# PSPS_AVNC_SRD_fullBoard-2020-09-19.net
KiCad netlist of a schematic drawn in EAGLE
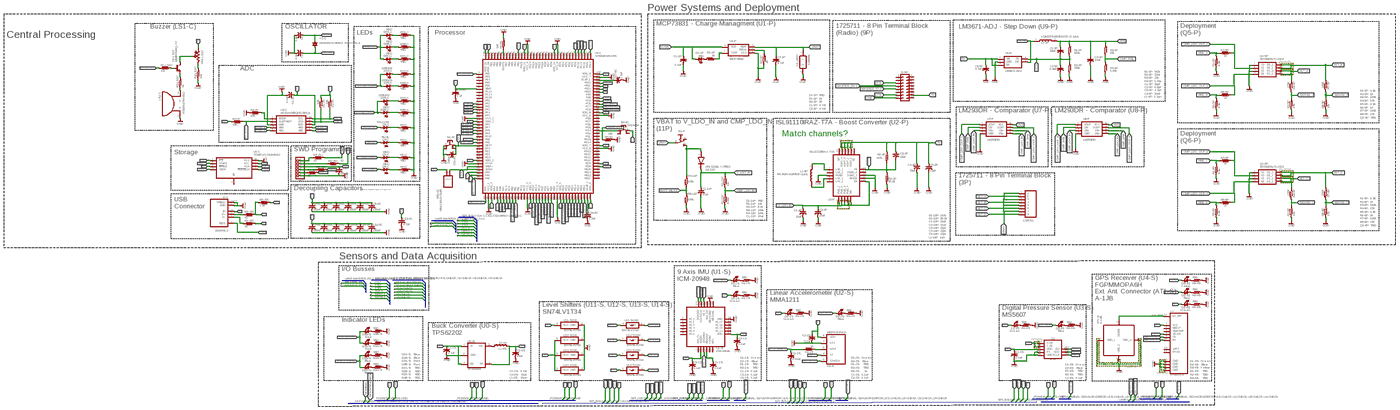
[diagram p0: schematic, sheet 1, overview]
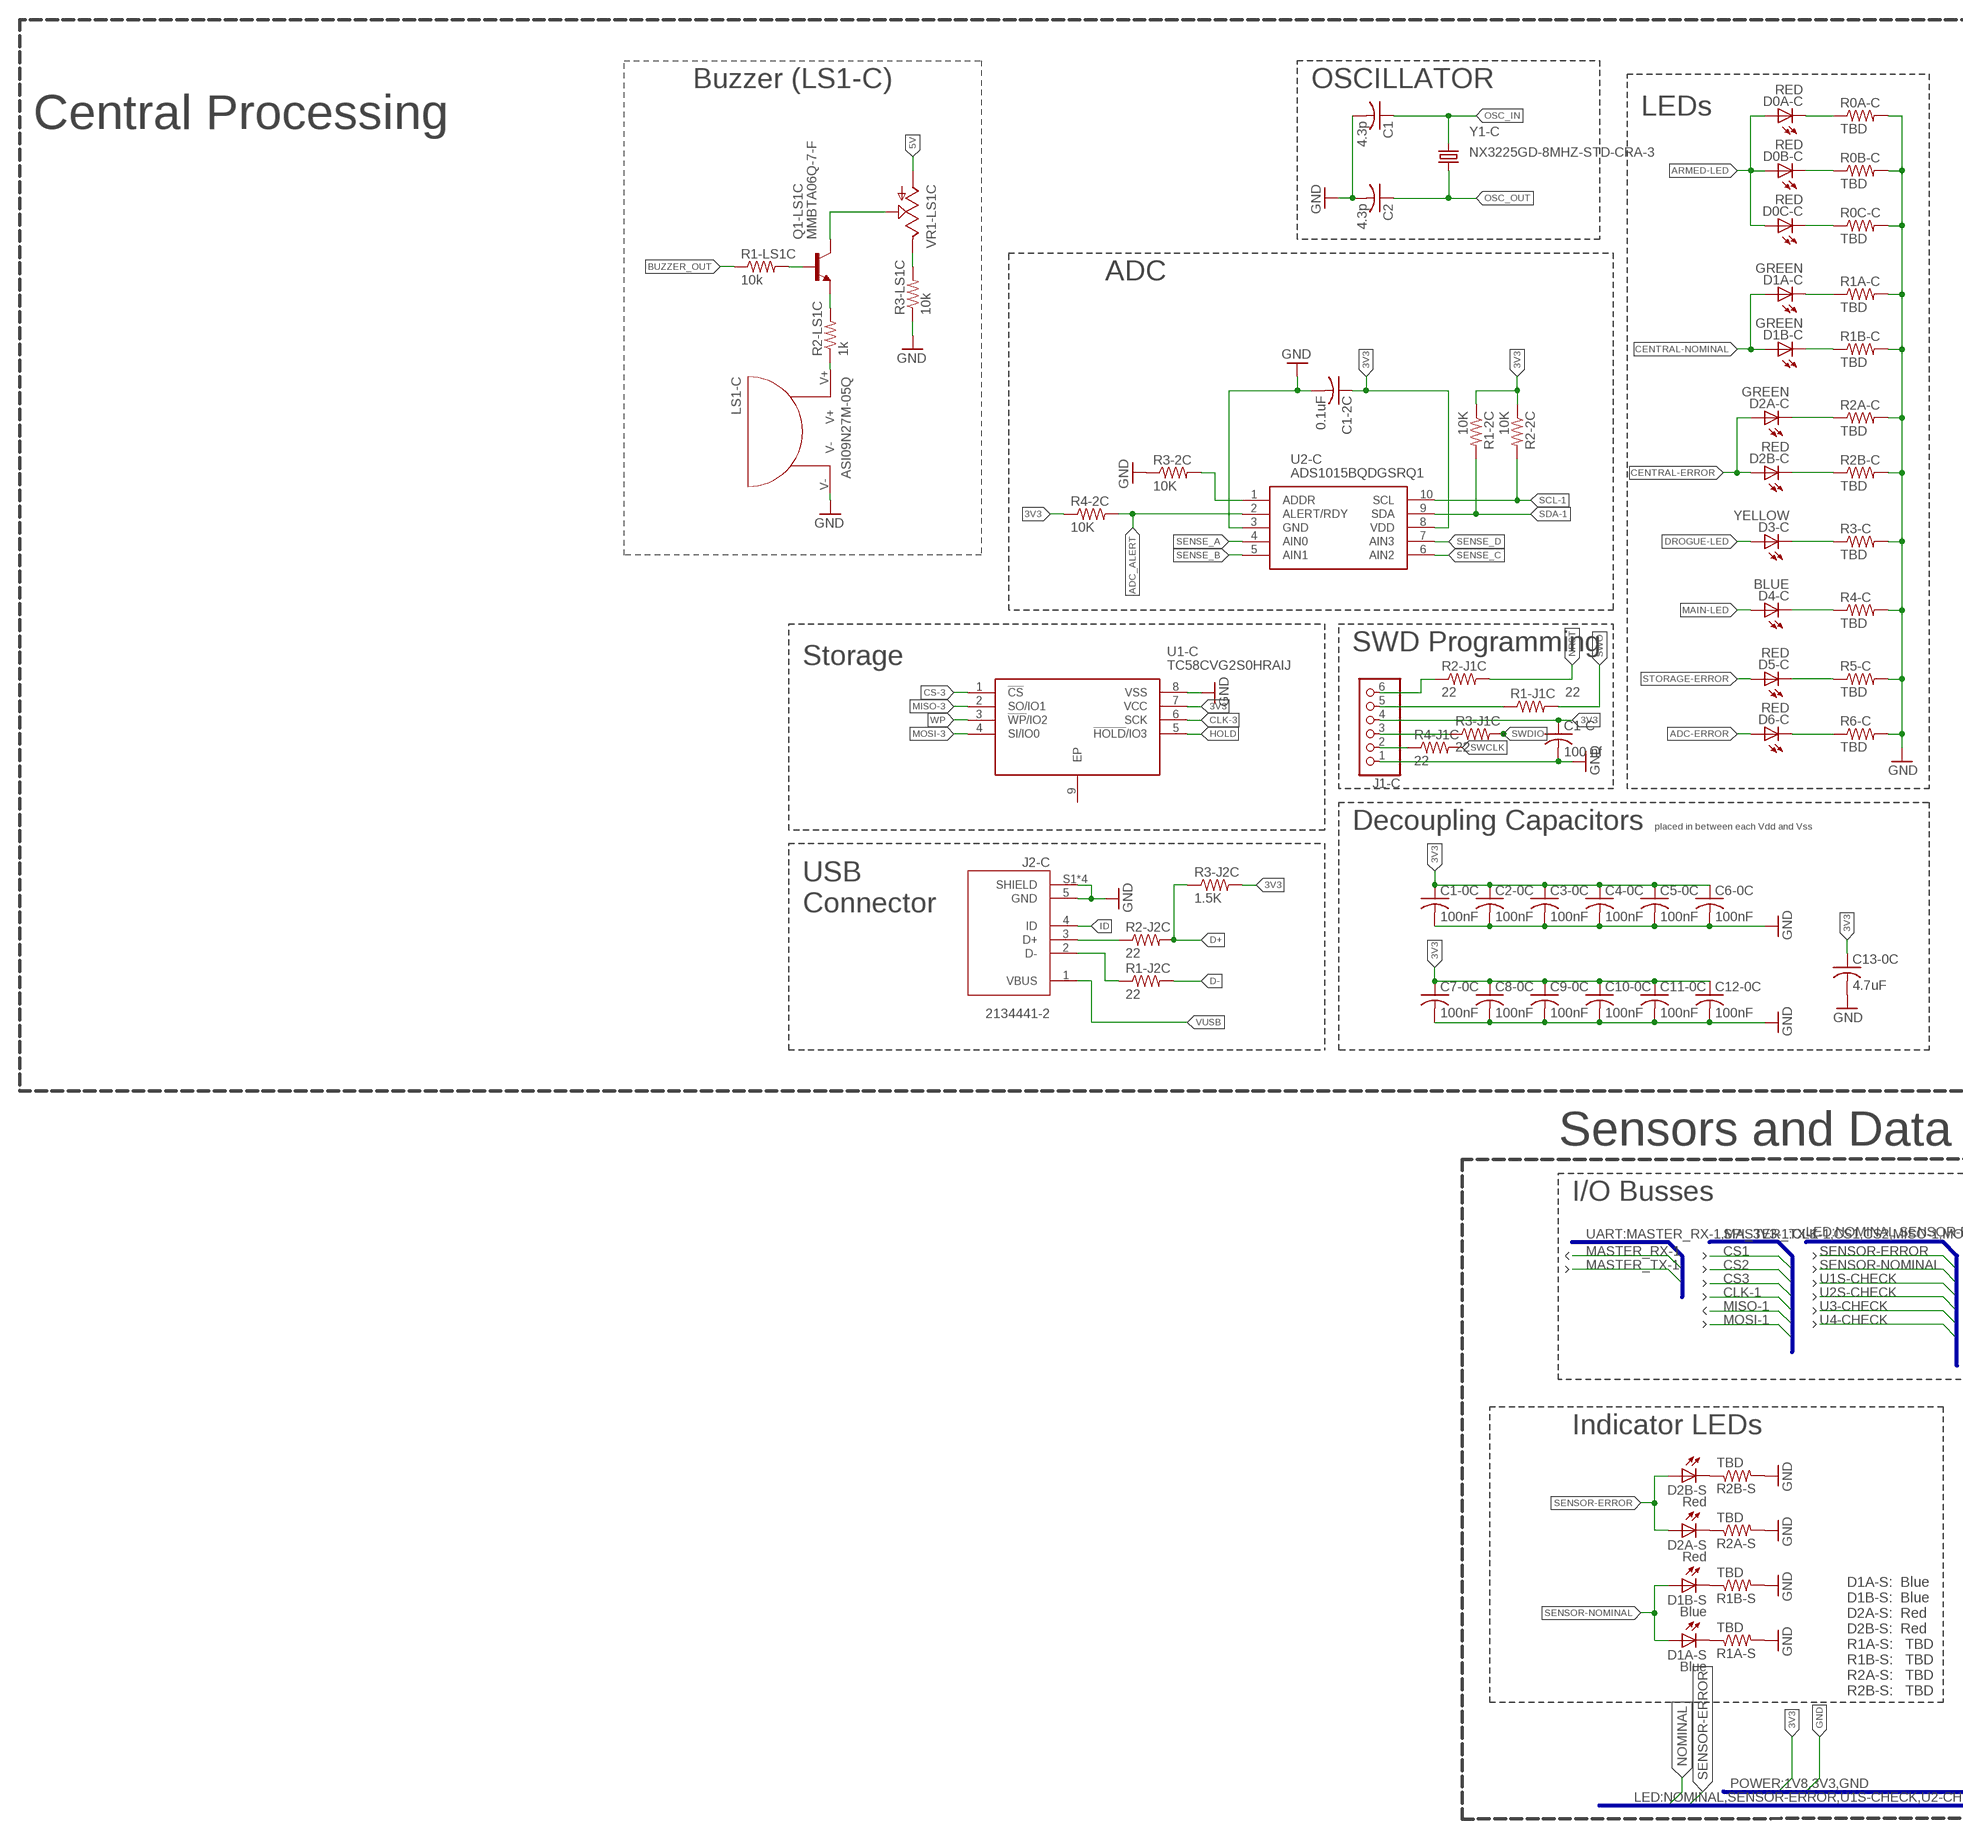
[diagram p1: schematic, sheet 1, part 1 of 4]
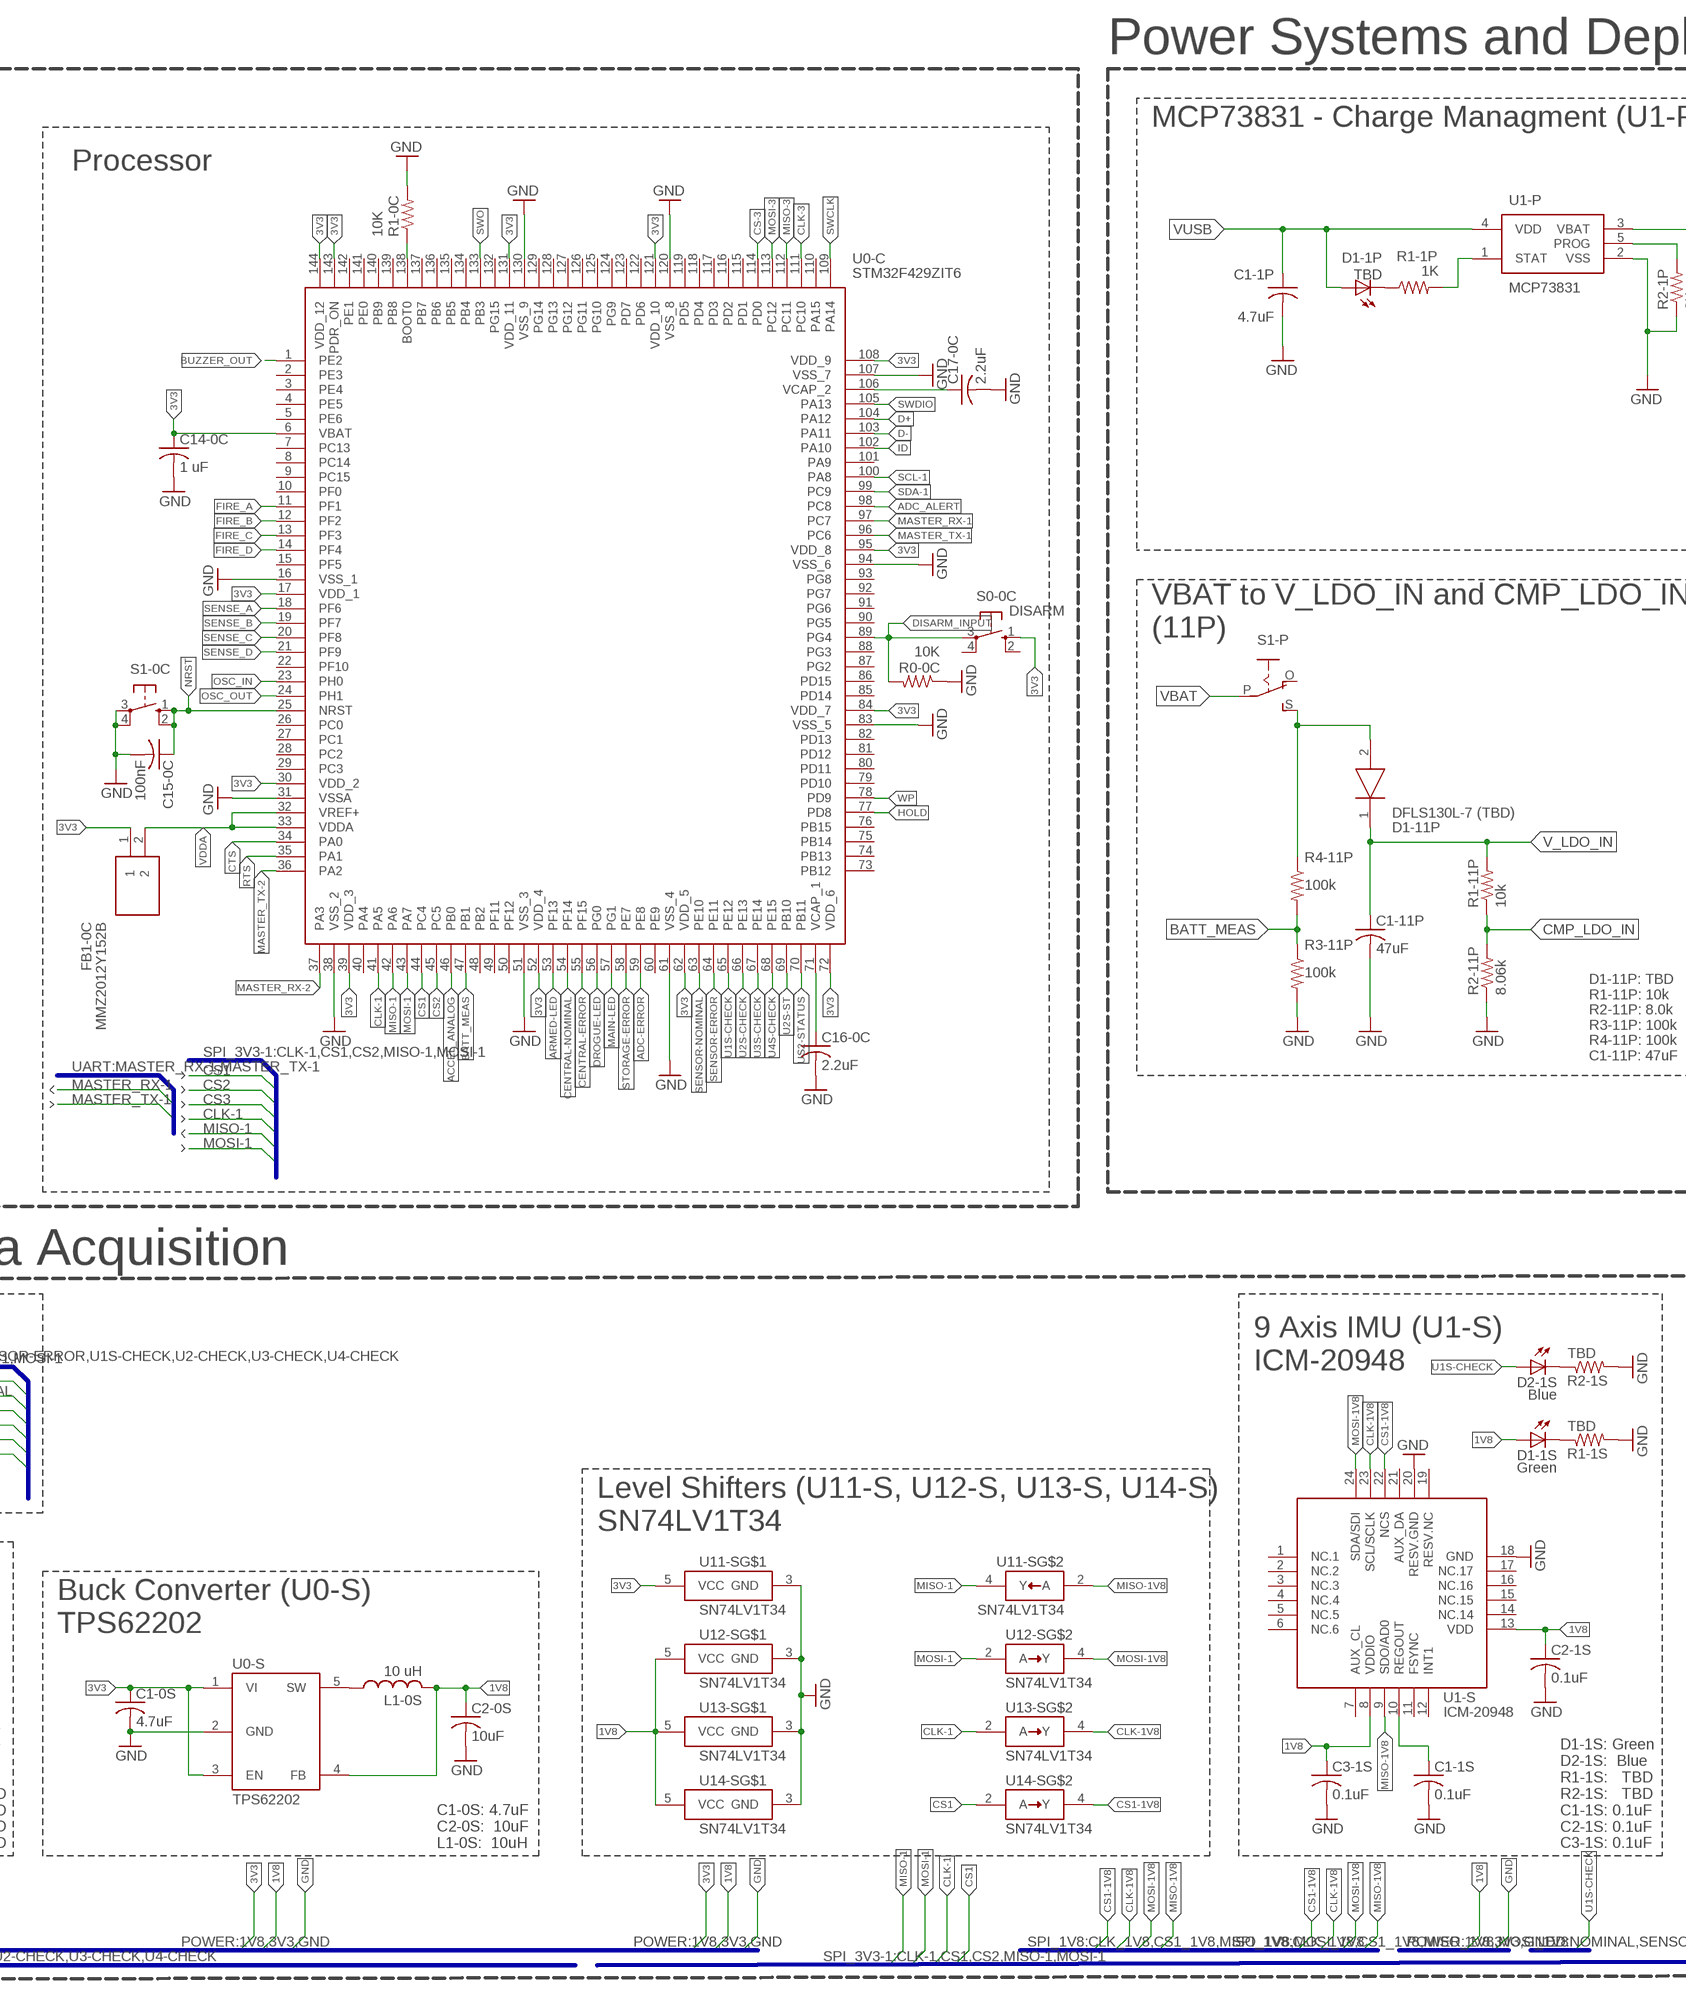
[diagram p2: schematic, sheet 1, part 2 of 4]
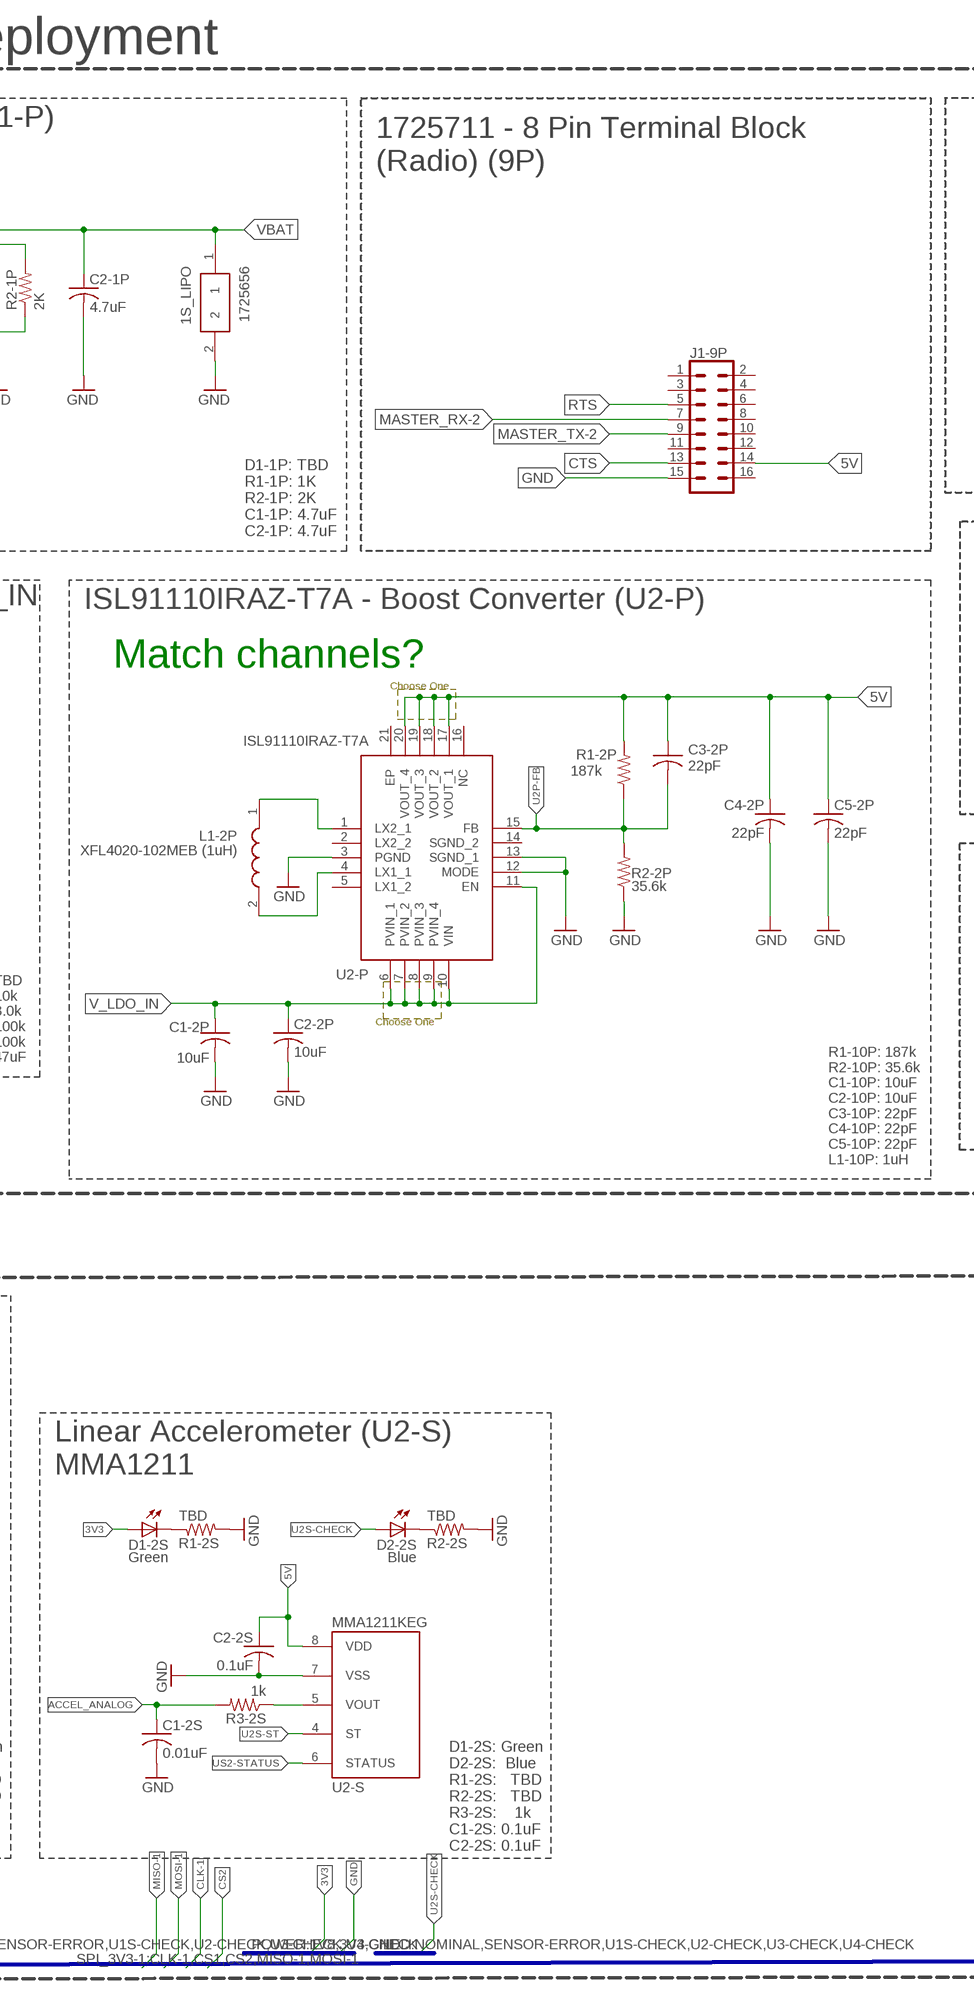
[diagram p3: schematic, sheet 1, part 3 of 4]
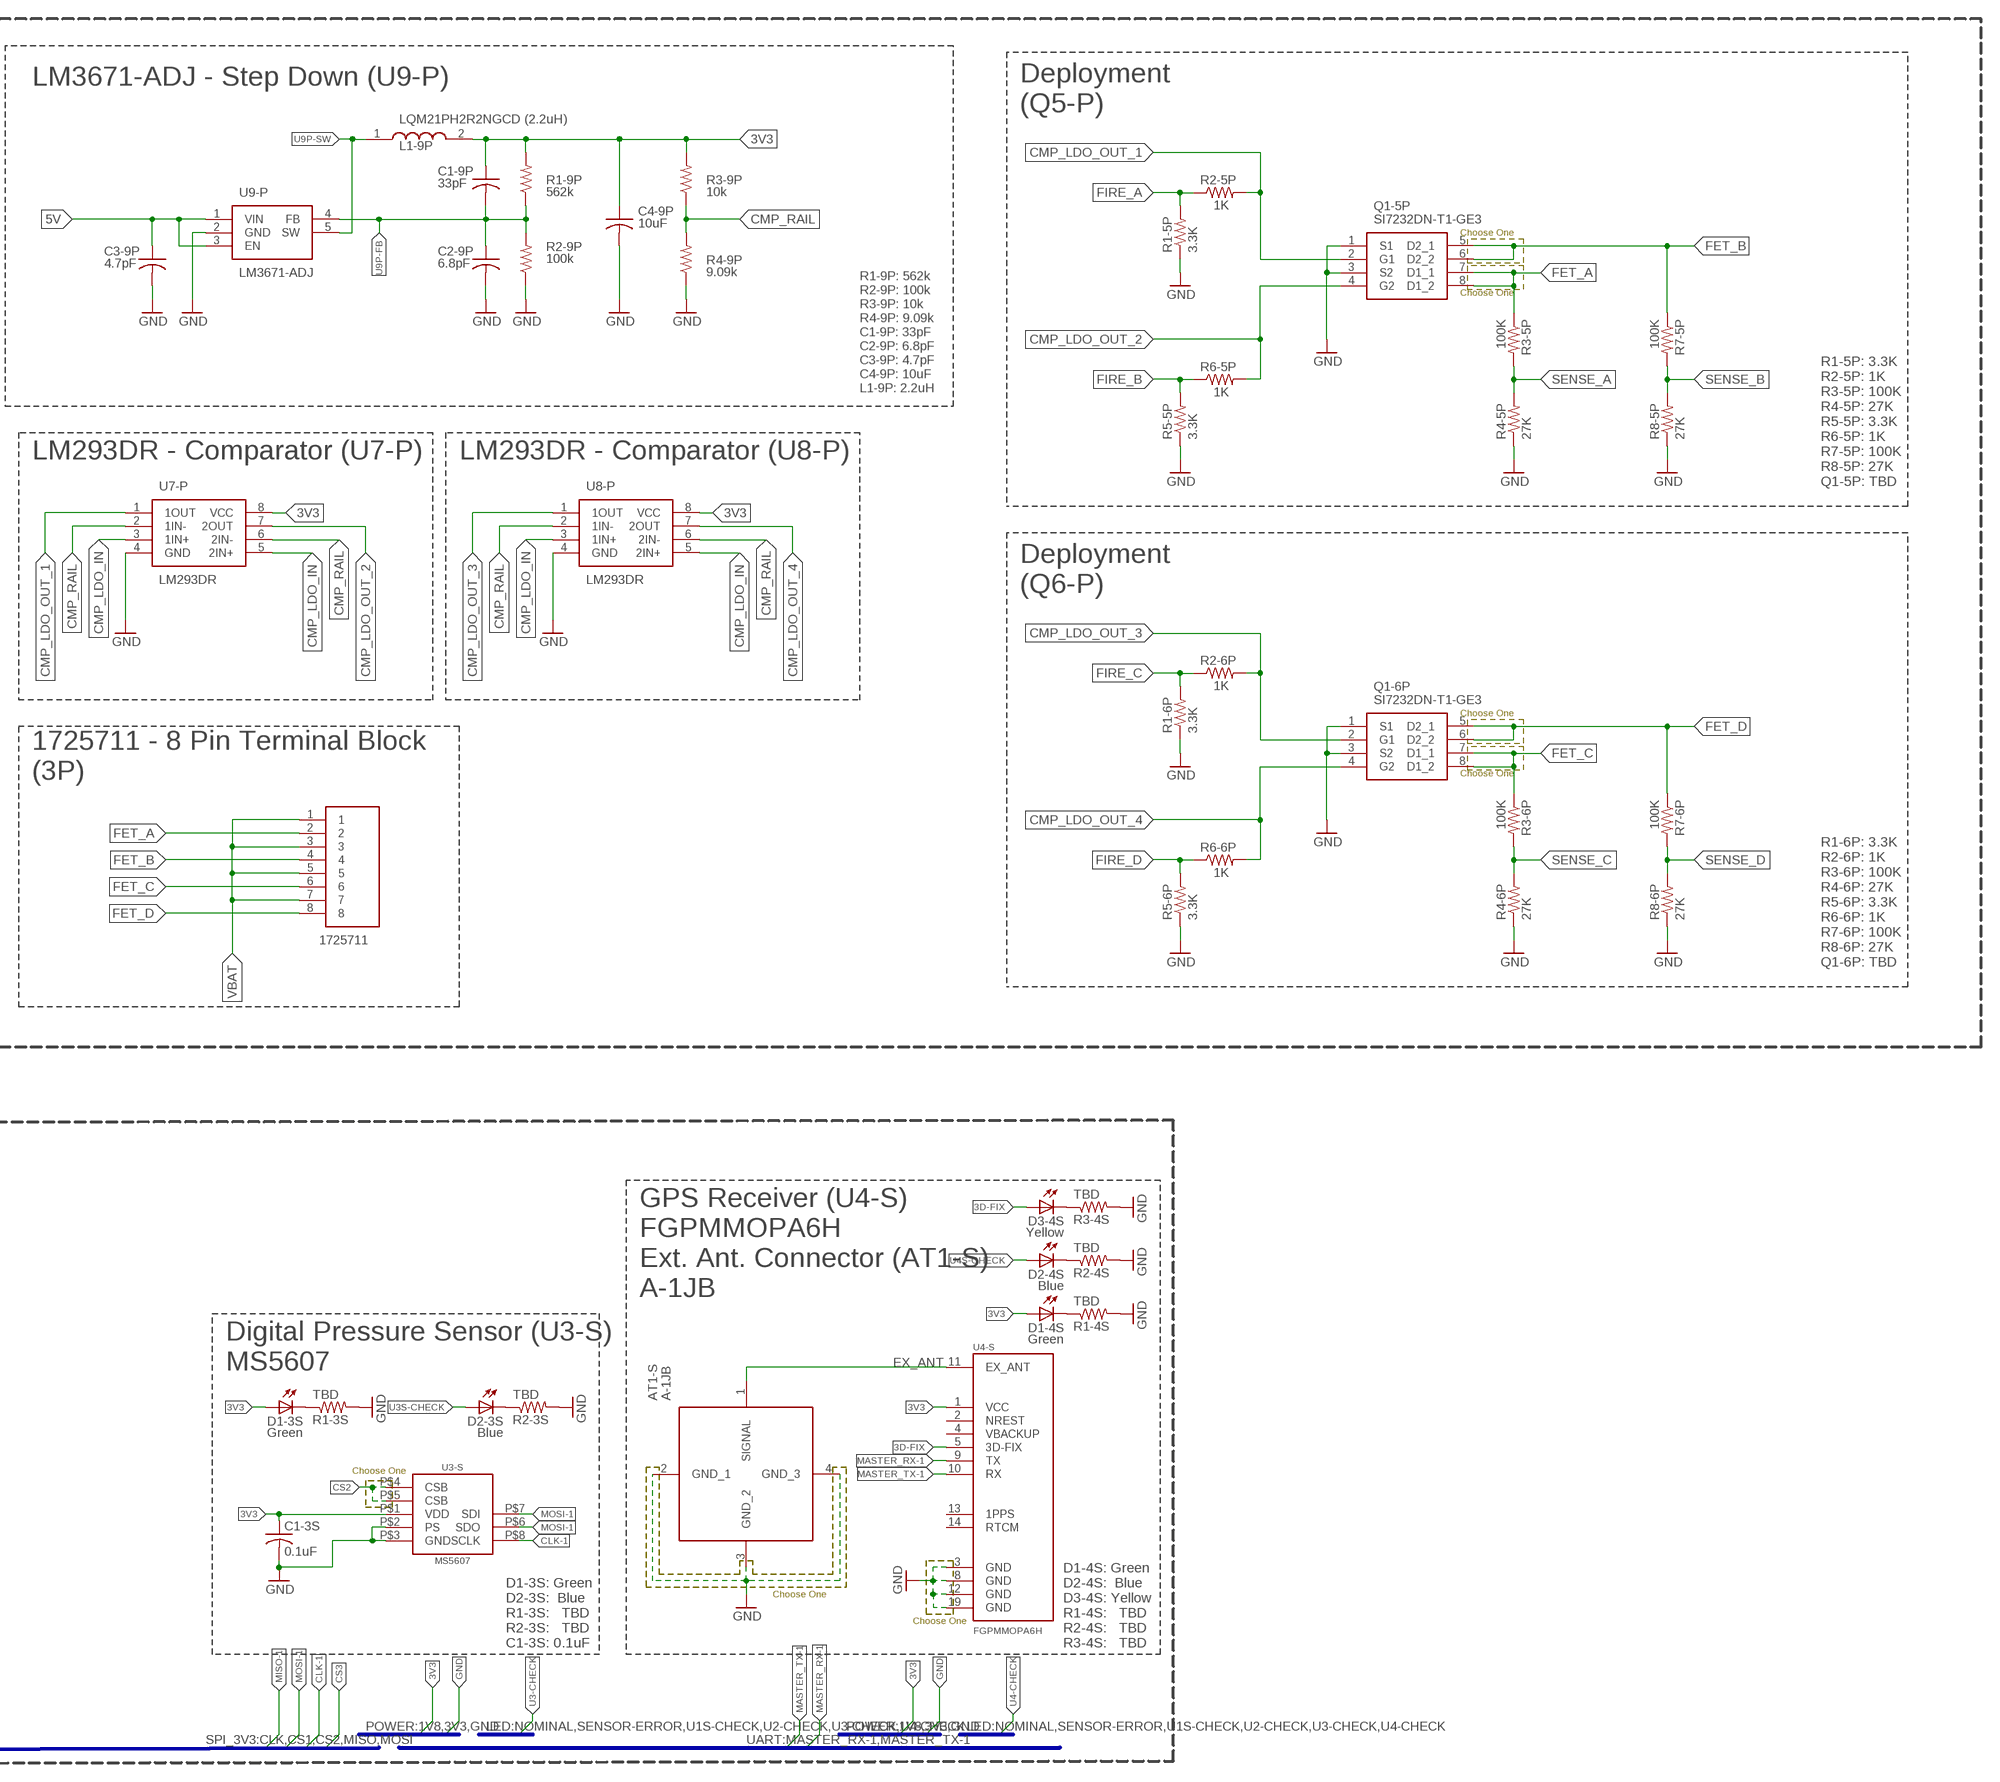
[diagram p4: schematic, sheet 1, part 4 of 4]

(export (version "E")
  (design (tool "Eeschema 10.0.6"))
  (components
    (comp (ref "1S_LIPO")
      (value "1725656")
      (footprint "eagle-import:1725656")
      (fields (field (name "MOUSER_PART_NUMBER") "651-1725656"))
      (libsource (lib "eagle-import") (part "1725656"))
    )
    (comp (ref "AT1-S")
      (value "A-1JB")
      (footprint "eagle-import:A1JB")
      (fields (field (name "MOUSER_PART_NUMBER") "523-A-1JB"))
      (libsource (lib "eagle-import") (part "A-1JB"))
    )
    (comp (ref "C1")
      (value "4.3p")
      (footprint "eagle-import:C0805")
      (libsource (lib "eagle-import") (part "rcl_334_C-USC0805"))
    )
    (comp (ref "C1-0C")
      (value "100nF")
      (footprint "eagle-import:C0805")
      (libsource (lib "eagle-import") (part "rcl_334_C-USC0805"))
    )
    (comp (ref "C1-0S")
      (value "4.7uF")
      (footprint "eagle-import:C0805")
      (libsource (lib "eagle-import") (part "resistor_348_C-USC0805"))
    )
    (comp (ref "C1-1P")
      (value "4.7uF")
      (footprint "eagle-import:C0805")
      (libsource (lib "eagle-import") (part "resistor_348_C-USC0805"))
    )
    (comp (ref "C1-1S")
      (value "0.1uF")
      (footprint "eagle-import:C0805")
      (libsource (lib "eagle-import") (part "resistor_348_C-USC0805"))
    )
    (comp (ref "C1-2C")
      (value "0.1uF")
      (footprint "eagle-import:C0805")
      (libsource (lib "eagle-import") (part "rcl_334_C-USC0805"))
    )
    (comp (ref "C1-2P")
      (value "10uF")
      (footprint "eagle-import:C0805")
      (libsource (lib "eagle-import") (part "resistor_348_C-USC0805"))
    )
    (comp (ref "C1-2S")
      (value "0.01uF")
      (footprint "eagle-import:C0805")
      (libsource (lib "eagle-import") (part "resistor_348_C-USC0805"))
    )
    (comp (ref "C1-3S")
      (value "0.1uF")
      (footprint "eagle-import:C0805")
      (libsource (lib "eagle-import") (part "resistor_348_C-USC0805"))
    )
    (comp (ref "C1-9P")
      (value "33pF")
      (footprint "eagle-import:C0805")
      (libsource (lib "eagle-import") (part "resistor_348_C-USC0805"))
    )
    (comp (ref "C1-11P")
      (value "47uF")
      (footprint "eagle-import:C0805")
      (libsource (lib "eagle-import") (part "resistor_348_C-USC0805"))
    )
    (comp (ref "C1-C")
      (value "100 nf")
      (footprint "eagle-import:C0805")
      (libsource (lib "eagle-import") (part "rcl_334_C-USC0805"))
    )
    (comp (ref "C2")
      (value "4.3p")
      (footprint "eagle-import:C0805")
      (libsource (lib "eagle-import") (part "rcl_334_C-USC0805"))
    )
    (comp (ref "C2-0C")
      (value "100nF")
      (footprint "eagle-import:C0805")
      (libsource (lib "eagle-import") (part "rcl_334_C-USC0805"))
    )
    (comp (ref "C2-0S")
      (value "10uF")
      (footprint "eagle-import:C0805")
      (libsource (lib "eagle-import") (part "resistor_348_C-USC0805"))
    )
    (comp (ref "C2-1P")
      (value "4.7uF")
      (footprint "eagle-import:C0805")
      (libsource (lib "eagle-import") (part "resistor_348_C-USC0805"))
    )
    (comp (ref "C2-1S")
      (value "0.1uF")
      (footprint "eagle-import:C0805")
      (libsource (lib "eagle-import") (part "resistor_348_C-USC0805"))
    )
    (comp (ref "C2-2P")
      (value "10uF")
      (footprint "eagle-import:C0805")
      (libsource (lib "eagle-import") (part "C-USC0805"))
    )
    (comp (ref "C2-2S")
      (value "0.1uF")
      (footprint "eagle-import:C0805")
      (libsource (lib "eagle-import") (part "resistor_348_C-USC0805"))
    )
    (comp (ref "C2-9P")
      (value "6.8pF")
      (footprint "eagle-import:C0805")
      (libsource (lib "eagle-import") (part "resistor_348_C-USC0805"))
    )
    (comp (ref "C3-0C")
      (value "100nF")
      (footprint "eagle-import:C0805")
      (libsource (lib "eagle-import") (part "rcl_334_C-USC0805"))
    )
    (comp (ref "C3-1S")
      (value "0.1uF")
      (footprint "eagle-import:C0805")
      (libsource (lib "eagle-import") (part "resistor_348_C-USC0805"))
    )
    (comp (ref "C3-2P")
      (value "22pF")
      (footprint "eagle-import:C0805")
      (libsource (lib "eagle-import") (part "resistor_348_C-USC0805"))
    )
    (comp (ref "C3-9P")
      (value "4.7pF")
      (footprint "eagle-import:C0805")
      (libsource (lib "eagle-import") (part "resistor_348_C-USC0805"))
    )
    (comp (ref "C4-0C")
      (value "100nF")
      (footprint "eagle-import:C0805")
      (libsource (lib "eagle-import") (part "rcl_334_C-USC0805"))
    )
    (comp (ref "C4-2P")
      (value "22pF")
      (footprint "eagle-import:C0805")
      (fields (field (name "SPICEPREFIX") "C"))
      (libsource (lib "eagle-import") (part "resistor_348_C-USC0805"))
    )
    (comp (ref "C4-9P")
      (value "10uF")
      (footprint "eagle-import:C0805")
      (libsource (lib "eagle-import") (part "resistor_348_C-USC0805"))
    )
    (comp (ref "C5-0C")
      (value "100nF")
      (footprint "eagle-import:C0805")
      (libsource (lib "eagle-import") (part "rcl_334_C-USC0805"))
    )
    (comp (ref "C5-2P")
      (value "22pF")
      (footprint "eagle-import:C0805")
      (libsource (lib "eagle-import") (part "C-USC0805"))
    )
    (comp (ref "C6-0C")
      (value "100nF")
      (footprint "eagle-import:C0805")
      (libsource (lib "eagle-import") (part "rcl_334_C-USC0805"))
    )
    (comp (ref "C7-0C")
      (value "100nF")
      (footprint "eagle-import:C0805")
      (libsource (lib "eagle-import") (part "rcl_334_C-USC0805"))
    )
    (comp (ref "C8-0C")
      (value "100nF")
      (footprint "eagle-import:C0805")
      (libsource (lib "eagle-import") (part "rcl_334_C-USC0805"))
    )
    (comp (ref "C9-0C")
      (value "100nF")
      (footprint "eagle-import:C0805")
      (libsource (lib "eagle-import") (part "rcl_334_C-USC0805"))
    )
    (comp (ref "C10-0C")
      (value "100nF")
      (footprint "eagle-import:C0805")
      (libsource (lib "eagle-import") (part "rcl_334_C-USC0805"))
    )
    (comp (ref "C11-0C")
      (value "100nF")
      (footprint "eagle-import:C0805")
      (libsource (lib "eagle-import") (part "rcl_334_C-USC0805"))
    )
    (comp (ref "C12-0C")
      (value "100nF")
      (footprint "eagle-import:C0805")
      (libsource (lib "eagle-import") (part "rcl_334_C-USC0805"))
    )
    (comp (ref "C13-0C")
      (value "4.7uF")
      (footprint "eagle-import:C0805")
      (libsource (lib "eagle-import") (part "rcl_334_C-USC0805"))
    )
    (comp (ref "C14-0C")
      (value "1 uF")
      (footprint "eagle-import:C0805")
      (libsource (lib "eagle-import") (part "rcl_334_C-USC0805"))
    )
    (comp (ref "C15-0C")
      (value "100nF")
      (footprint "eagle-import:C0805")
      (libsource (lib "eagle-import") (part "rcl_334_C-USC0805"))
    )
    (comp (ref "C16-0C")
      (value "2.2uF")
      (footprint "eagle-import:C0805")
      (libsource (lib "eagle-import") (part "rcl_334_C-USC0805"))
    )
    (comp (ref "C17-0C")
      (value "2.2uF")
      (footprint "eagle-import:C0805")
      (libsource (lib "eagle-import") (part "rcl_334_C-USC0805"))
    )
    (comp (ref "D0A-C")
      (value "RED")
      (footprint "eagle-import:CHIPLED_0805")
      (libsource (lib "eagle-import") (part "adafruit_420_LEDCHIPLED_0805"))
    )
    (comp (ref "D0B-C")
      (value "RED")
      (footprint "eagle-import:CHIPLED_0805")
      (libsource (lib "eagle-import") (part "adafruit_420_LEDCHIPLED_0805"))
    )
    (comp (ref "D0C-C")
      (value "RED")
      (footprint "eagle-import:CHIPLED_0805")
      (libsource (lib "eagle-import") (part "adafruit_420_LEDCHIPLED_0805"))
    )
    (comp (ref "D1-1P")
      (value "TBD")
      (footprint "eagle-import:CHIPLED_0805")
      (libsource (lib "eagle-import") (part "adafruit_420_LEDCHIPLED_0805"))
    )
    (comp (ref "D1-1S")
      (value "Green")
      (footprint "eagle-import:CHIPLED_0805")
      (libsource (lib "eagle-import") (part "LEDCHIPLED_0805"))
    )
    (comp (ref "D1-2S")
      (value "Green")
      (footprint "eagle-import:CHIPLED_0805")
      (libsource (lib "eagle-import") (part "LEDCHIPLED_0805"))
    )
    (comp (ref "D1-3S")
      (value "Green")
      (footprint "eagle-import:CHIPLED_0805")
      (libsource (lib "eagle-import") (part "LEDCHIPLED_0805"))
    )
    (comp (ref "D1-4S")
      (value "Green")
      (footprint "eagle-import:CHIPLED_0805")
      (libsource (lib "eagle-import") (part "LEDCHIPLED_0805"))
    )
    (comp (ref "D1-11P")
      (value "DFLS130L-7 (TBD)")
      (footprint "eagle-import:POWERDI_123")
      (fields
        (field (name "MANUFACTURER_PART_NUMBER") "DFLS130L-7")
        (field (name "MOUSER_PART_NUMBER") "621-DFLS130L")
      )
      (libsource (lib "eagle-import") (part "DFLS130L-7"))
    )
    (comp (ref "D1A-C")
      (value "GREEN")
      (footprint "eagle-import:CHIPLED_0805")
      (libsource (lib "eagle-import") (part "adafruit_420_LEDCHIPLED_0805"))
    )
    (comp (ref "D1A-S")
      (value "Blue")
      (footprint "eagle-import:CHIPLED_0805")
      (libsource (lib "eagle-import") (part "LEDCHIPLED_0805"))
    )
    (comp (ref "D1B-C")
      (value "GREEN")
      (footprint "eagle-import:CHIPLED_0805")
      (libsource (lib "eagle-import") (part "adafruit_420_LEDCHIPLED_0805"))
    )
    (comp (ref "D1B-S")
      (value "Blue")
      (footprint "eagle-import:CHIPLED_0805")
      (libsource (lib "eagle-import") (part "LEDCHIPLED_0805"))
    )
    (comp (ref "D2-1S")
      (value "Blue")
      (footprint "eagle-import:CHIPLED_0805")
      (libsource (lib "eagle-import") (part "LEDCHIPLED_0805"))
    )
    (comp (ref "D2-2S")
      (value "Blue")
      (footprint "eagle-import:CHIPLED_0805")
      (libsource (lib "eagle-import") (part "LEDCHIPLED_0805"))
    )
    (comp (ref "D2-3S")
      (value "Blue")
      (footprint "eagle-import:CHIPLED_0805")
      (libsource (lib "eagle-import") (part "LEDCHIPLED_0805"))
    )
    (comp (ref "D2-4S")
      (value "Blue")
      (footprint "eagle-import:CHIPLED_0805")
      (libsource (lib "eagle-import") (part "LEDCHIPLED_0805"))
    )
    (comp (ref "D2A-C")
      (value "GREEN")
      (footprint "eagle-import:CHIPLED_0805")
      (libsource (lib "eagle-import") (part "adafruit_420_LEDCHIPLED_0805"))
    )
    (comp (ref "D2A-S")
      (value "Red")
      (footprint "eagle-import:CHIPLED_0805")
      (libsource (lib "eagle-import") (part "LEDCHIPLED_0805"))
    )
    (comp (ref "D2B-C")
      (value "RED")
      (footprint "eagle-import:CHIPLED_0805")
      (libsource (lib "eagle-import") (part "adafruit_420_LEDCHIPLED_0805"))
    )
    (comp (ref "D2B-S")
      (value "Red")
      (footprint "eagle-import:CHIPLED_0805")
      (libsource (lib "eagle-import") (part "LEDCHIPLED_0805"))
    )
    (comp (ref "D3-4S")
      (value "Yellow")
      (footprint "eagle-import:CHIPLED_0805")
      (libsource (lib "eagle-import") (part "LEDCHIPLED_0805"))
    )
    (comp (ref "D3-C")
      (value "YELLOW")
      (footprint "eagle-import:CHIPLED_0805")
      (libsource (lib "eagle-import") (part "adafruit_420_LEDCHIPLED_0805"))
    )
    (comp (ref "D4-C")
      (value "BLUE")
      (footprint "eagle-import:CHIPLED_0805")
      (libsource (lib "eagle-import") (part "adafruit_420_LEDCHIPLED_0805"))
    )
    (comp (ref "D5-C")
      (value "RED")
      (footprint "eagle-import:CHIPLED_0805")
      (libsource (lib "eagle-import") (part "adafruit_420_LEDCHIPLED_0805"))
    )
    (comp (ref "D6-C")
      (value "RED")
      (footprint "eagle-import:CHIPLED_0805")
      (libsource (lib "eagle-import") (part "adafruit_420_LEDCHIPLED_0805"))
    )
    (comp (ref "FB1-0C")
      (value "MMZ2012Y152B")
      (footprint "eagle-import:BEADC2012X105N")
      (fields (field (name "MOUSER_PART_NUMBER") "810-MMZ2012Y152B"))
      (libsource (lib "eagle-import") (part "MMZ2012Y152B"))
    )
    (comp (ref "J1-9P")
      (value "CONN_08X2")
      (footprint "eagle-import:2X8")
      (libsource (lib "eagle-import") (part "CONN_08X2"))
    )
    (comp (ref "J1-C")
      (value "PINHD-1X6")
      (footprint "eagle-import:1X06")
      (libsource (lib "eagle-import") (part "PINHD-1X6"))
    )
    (comp (ref "J2-C")
      (value "2134441-2")
      (footprint "eagle-import:TE_2134441-2")
      (fields (field (name "DIGI-KEY_PART_NUMBER") "A118104CT-ND") (field (name "MF") "TE Connectivity"))
      (libsource (lib "eagle-import") (part "2134441-2"))
    )
    (comp (ref "J2-P")
      (value "1725711")
      (footprint "eagle-import:1725711")
      (fields (field (name "MOUSER_PART_NUMBER") "651-1725711"))
      (libsource (lib "eagle-import") (part "1725711"))
    )
    (comp (ref "L1-0S")
      (value "10 uH")
      (footprint "eagle-import:PF0560NL")
      (libsource (lib "eagle-import") (part "PF0560.103NLT"))
    )
    (comp (ref "L1-2P")
      (value "XFL4020-102MEB (1uH)")
      (footprint "eagle-import:XFL4020")
      (fields
        (field (name "MANUFACTURER_PART_NUMBER") "XFL4020-102MEB")
        (field (name "MOUSER_PART_NUMBER") "994-XFL4020-102MEB")
      )
      (libsource (lib "eagle-import") (part "XFL4020-102MEB"))
    )
    (comp (ref "L1-9P")
      (value "LQM21PH2R2NGCD (2.2uH)")
      (footprint "eagle-import:INDC2012X100N")
      (fields
        (field (name "MANUFACTURER_PART_NUMBER") "LQM21PH2R2NGCD")
        (field (name "MOUSER_PART_NUMBER") "81-LQM21PH2R2NGCD")
      )
      (libsource (lib "eagle-import") (part "LQM21PH2R2NGCD"))
    )
    (comp (ref "LS1-C")
      (value "ASI09N27M-05Q")
      (footprint "eagle-import:ASI09N27M-05Q")
      (libsource (lib "eagle-import") (part "ASI09N27M-05Q"))
    )
    (comp (ref "Q1-5P")
      (value "SI7232DN-T1-GE3")
      (footprint "eagle-import:POWERPAK-1212-8")
      (fields (field (name "MOUSER_PART_NUMBER") "781-SI7232DN-GE3"))
      (libsource (lib "eagle-import") (part "SI7232DN-T1-GE3"))
    )
    (comp (ref "Q1-6P")
      (value "SI7232DN-T1-GE3")
      (footprint "eagle-import:POWERPAK-1212-8")
      (fields (field (name "MOUSER_PART_NUMBER") "781-SI7232DN-GE3"))
      (libsource (lib "eagle-import") (part "SI7232DN-T1-GE3"))
    )
    (comp (ref "Q1-LS1C")
      (value "MMBTA06Q-7-F")
      (footprint "eagle-import:SOT23")
      (libsource (lib "eagle-import") (part "NPN_TRANSISTOR"))
    )
    (comp (ref "R0-0C")
      (value "10K")
      (footprint "eagle-import:R0805")
      (libsource (lib "eagle-import") (part "rcl_334_R-US_R0805"))
    )
    (comp (ref "R0A-C")
      (value "TBD")
      (footprint "eagle-import:M0805")
      (libsource (lib "eagle-import") (part "rcl_334_R-US_M0805"))
    )
    (comp (ref "R0B-C")
      (value "TBD")
      (footprint "eagle-import:M0805")
      (libsource (lib "eagle-import") (part "rcl_334_R-US_M0805"))
    )
    (comp (ref "R0C-C")
      (value "TBD")
      (footprint "eagle-import:M0805")
      (libsource (lib "eagle-import") (part "rcl_334_R-US_M0805"))
    )
    (comp (ref "R1-0C")
      (value "10K")
      (footprint "eagle-import:R0805")
      (libsource (lib "eagle-import") (part "rcl_334_R-US_R0805"))
    )
    (comp (ref "R1-1P")
      (value "1K")
      (footprint "eagle-import:R0805")
      (libsource (lib "eagle-import") (part "resistor_348_R-US_R0805"))
    )
    (comp (ref "R1-1S")
      (value "TBD")
      (footprint "eagle-import:R0805")
      (libsource (lib "eagle-import") (part "resistor_348_R-US_R0805"))
    )
    (comp (ref "R1-2C")
      (value "10K")
      (footprint "eagle-import:R0805")
      (libsource (lib "eagle-import") (part "rcl_334_R-US_R0805"))
    )
    (comp (ref "R1-2P")
      (value "187k")
      (footprint "eagle-import:R0805")
      (libsource (lib "eagle-import") (part "resistor_348_R-US_R0805"))
    )
    (comp (ref "R1-2S")
      (value "TBD")
      (footprint "eagle-import:R0805")
      (libsource (lib "eagle-import") (part "resistor_348_R-US_R0805"))
    )
    (comp (ref "R1-3S")
      (value "TBD")
      (footprint "eagle-import:R0805")
      (libsource (lib "eagle-import") (part "resistor_348_R-US_R0805"))
    )
    (comp (ref "R1-4S")
      (value "TBD")
      (footprint "eagle-import:R0805")
      (libsource (lib "eagle-import") (part "resistor_348_R-US_R0805"))
    )
    (comp (ref "R1-5P")
      (value "3.3K")
      (footprint "eagle-import:M0805")
      (libsource (lib "eagle-import") (part "rcl_334_R-US_M0805"))
    )
    (comp (ref "R1-6P")
      (value "3.3K")
      (footprint "eagle-import:M0805")
      (libsource (lib "eagle-import") (part "rcl_334_R-US_M0805"))
    )
    (comp (ref "R1-9P")
      (value "562k")
      (footprint "eagle-import:R0805")
      (libsource (lib "eagle-import") (part "resistor_348_R-US_R0805"))
    )
    (comp (ref "R1-11P")
      (value "10k")
      (footprint "eagle-import:R0805")
      (libsource (lib "eagle-import") (part "resistor_348_R-US_R0805"))
    )
    (comp (ref "R1-J1C")
      (value "22")
      (footprint "eagle-import:M0805")
      (libsource (lib "eagle-import") (part "rcl_334_R-US_M0805"))
    )
    (comp (ref "R1-J2C")
      (value "22")
      (footprint "eagle-import:M0805")
      (libsource (lib "eagle-import") (part "rcl_334_R-US_M0805"))
    )
    (comp (ref "R1-LS1C")
      (value "10k")
      (footprint "eagle-import:R0805")
      (libsource (lib "eagle-import") (part "resistor_348_R-US_R0805"))
    )
    (comp (ref "R1A-C")
      (value "TBD")
      (footprint "eagle-import:M0805")
      (libsource (lib "eagle-import") (part "rcl_334_R-US_M0805"))
    )
    (comp (ref "R1A-S")
      (value "TBD")
      (footprint "eagle-import:R0805")
      (libsource (lib "eagle-import") (part "resistor_348_R-US_R0805"))
    )
    (comp (ref "R1B-C")
      (value "TBD")
      (footprint "eagle-import:M0805")
      (libsource (lib "eagle-import") (part "rcl_334_R-US_M0805"))
    )
    (comp (ref "R1B-S")
      (value "TBD")
      (footprint "eagle-import:R0805")
      (libsource (lib "eagle-import") (part "resistor_348_R-US_R0805"))
    )
    (comp (ref "R2-1P")
      (value "2K")
      (footprint "eagle-import:R0805")
      (libsource (lib "eagle-import") (part "resistor_348_R-US_R0805"))
    )
    (comp (ref "R2-1S")
      (value "TBD")
      (footprint "eagle-import:R0805")
      (libsource (lib "eagle-import") (part "resistor_348_R-US_R0805"))
    )
    (comp (ref "R2-2C")
      (value "10K")
      (footprint "eagle-import:R0805")
      (libsource (lib "eagle-import") (part "rcl_334_R-US_R0805"))
    )
    (comp (ref "R2-2P")
      (value "35.6k")
      (footprint "eagle-import:R0805")
      (libsource (lib "eagle-import") (part "resistor_348_R-US_R0805"))
    )
    (comp (ref "R2-2S")
      (value "TBD")
      (footprint "eagle-import:R0805")
      (libsource (lib "eagle-import") (part "resistor_348_R-US_R0805"))
    )
    (comp (ref "R2-3S")
      (value "TBD")
      (footprint "eagle-import:R0805")
      (libsource (lib "eagle-import") (part "resistor_348_R-US_R0805"))
    )
    (comp (ref "R2-4S")
      (value "TBD")
      (footprint "eagle-import:R0805")
      (libsource (lib "eagle-import") (part "resistor_348_R-US_R0805"))
    )
    (comp (ref "R2-5P")
      (value "1K")
      (footprint "eagle-import:M0805")
      (libsource (lib "eagle-import") (part "rcl_334_R-US_M0805"))
    )
    (comp (ref "R2-6P")
      (value "1K")
      (footprint "eagle-import:M0805")
      (libsource (lib "eagle-import") (part "rcl_334_R-US_M0805"))
    )
    (comp (ref "R2-9P")
      (value "100k")
      (footprint "eagle-import:R0805")
      (libsource (lib "eagle-import") (part "resistor_348_R-US_R0805"))
    )
    (comp (ref "R2-11P")
      (value "8.06k")
      (footprint "eagle-import:R0805")
      (libsource (lib "eagle-import") (part "resistor_348_R-US_R0805"))
    )
    (comp (ref "R2-J1C")
      (value "22")
      (footprint "eagle-import:M0805")
      (libsource (lib "eagle-import") (part "rcl_334_R-US_M0805"))
    )
    (comp (ref "R2-J2C")
      (value "22")
      (footprint "eagle-import:M0805")
      (libsource (lib "eagle-import") (part "rcl_334_R-US_M0805"))
    )
    (comp (ref "R2-LS1C")
      (value "1k")
      (footprint "eagle-import:R0805")
      (libsource (lib "eagle-import") (part "resistor_348_R-US_R0805"))
    )
    (comp (ref "R2A-C")
      (value "TBD")
      (footprint "eagle-import:M0805")
      (libsource (lib "eagle-import") (part "rcl_334_R-US_M0805"))
    )
    (comp (ref "R2A-S")
      (value "TBD")
      (footprint "eagle-import:R0805")
      (libsource (lib "eagle-import") (part "resistor_348_R-US_R0805"))
    )
    (comp (ref "R2B-C")
      (value "TBD")
      (footprint "eagle-import:M0805")
      (libsource (lib "eagle-import") (part "rcl_334_R-US_M0805"))
    )
    (comp (ref "R2B-S")
      (value "TBD")
      (footprint "eagle-import:R0805")
      (libsource (lib "eagle-import") (part "resistor_348_R-US_R0805"))
    )
    (comp (ref "R3-2C")
      (value "10K")
      (footprint "eagle-import:R0805")
      (libsource (lib "eagle-import") (part "rcl_334_R-US_R0805"))
    )
    (comp (ref "R3-2S")
      (value "1k")
      (footprint "eagle-import:R0805")
      (libsource (lib "eagle-import") (part "resistor_348_R-US_R0805"))
    )
    (comp (ref "R3-4S")
      (value "TBD")
      (footprint "eagle-import:R0805")
      (libsource (lib "eagle-import") (part "resistor_348_R-US_R0805"))
    )
    (comp (ref "R3-5P")
      (value "100K")
      (footprint "eagle-import:M0805")
      (libsource (lib "eagle-import") (part "rcl_334_R-US_M0805"))
    )
    (comp (ref "R3-6P")
      (value "100K")
      (footprint "eagle-import:M0805")
      (libsource (lib "eagle-import") (part "rcl_334_R-US_M0805"))
    )
    (comp (ref "R3-9P")
      (value "10k")
      (footprint "eagle-import:R0805")
      (libsource (lib "eagle-import") (part "resistor_348_R-US_R0805"))
    )
    (comp (ref "R3-11P")
      (value "100k")
      (footprint "eagle-import:R0805")
      (libsource (lib "eagle-import") (part "R-US_R0805"))
    )
    (comp (ref "R3-C")
      (value "TBD")
      (footprint "eagle-import:M0805")
      (libsource (lib "eagle-import") (part "rcl_334_R-US_M0805"))
    )
    (comp (ref "R3-J1C")
      (value "22")
      (footprint "eagle-import:M0805")
      (libsource (lib "eagle-import") (part "rcl_334_R-US_M0805"))
    )
    (comp (ref "R3-J2C")
      (value "1.5K")
      (footprint "eagle-import:M0805")
      (libsource (lib "eagle-import") (part "rcl_334_R-US_M0805"))
    )
    (comp (ref "R3-LS1C")
      (value "10k")
      (footprint "eagle-import:R0805")
      (libsource (lib "eagle-import") (part "resistor_348_R-US_R0805"))
    )
    (comp (ref "R4-2C")
      (value "10K")
      (footprint "eagle-import:R0805")
      (libsource (lib "eagle-import") (part "rcl_334_R-US_R0805"))
    )
    (comp (ref "R4-5P")
      (value "27K")
      (footprint "eagle-import:M0805")
      (libsource (lib "eagle-import") (part "rcl_334_R-US_M0805"))
    )
    (comp (ref "R4-6P")
      (value "27K")
      (footprint "eagle-import:M0805")
      (libsource (lib "eagle-import") (part "rcl_334_R-US_M0805"))
    )
    (comp (ref "R4-9P")
      (value "9.09k")
      (footprint "eagle-import:R0805")
      (libsource (lib "eagle-import") (part "resistor_348_R-US_R0805"))
    )
    (comp (ref "R4-11P")
      (value "100k")
      (footprint "eagle-import:R0805")
      (libsource (lib "eagle-import") (part "R-US_R0805"))
    )
    (comp (ref "R4-C")
      (value "TBD")
      (footprint "eagle-import:M0805")
      (libsource (lib "eagle-import") (part "rcl_334_R-US_M0805"))
    )
    (comp (ref "R4-J1C")
      (value "22")
      (footprint "eagle-import:M0805")
      (libsource (lib "eagle-import") (part "rcl_334_R-US_M0805"))
    )
    (comp (ref "R5-5P")
      (value "3.3K")
      (footprint "eagle-import:M0805")
      (libsource (lib "eagle-import") (part "rcl_334_R-US_M0805"))
    )
    (comp (ref "R5-6P")
      (value "3.3K")
      (footprint "eagle-import:M0805")
      (libsource (lib "eagle-import") (part "rcl_334_R-US_M0805"))
    )
    (comp (ref "R5-C")
      (value "TBD")
      (footprint "eagle-import:M0805")
      (libsource (lib "eagle-import") (part "rcl_334_R-US_M0805"))
    )
    (comp (ref "R6-5P")
      (value "1K")
      (footprint "eagle-import:M0805")
      (libsource (lib "eagle-import") (part "rcl_334_R-US_M0805"))
    )
    (comp (ref "R6-6P")
      (value "1K")
      (footprint "eagle-import:M0805")
      (libsource (lib "eagle-import") (part "rcl_334_R-US_M0805"))
    )
    (comp (ref "R6-C")
      (value "TBD")
      (footprint "eagle-import:M0805")
      (libsource (lib "eagle-import") (part "rcl_334_R-US_M0805"))
    )
    (comp (ref "R7-5P")
      (value "100K")
      (footprint "eagle-import:M0805")
      (libsource (lib "eagle-import") (part "rcl_334_R-US_M0805"))
    )
    (comp (ref "R7-6P")
      (value "100K")
      (footprint "eagle-import:M0805")
      (libsource (lib "eagle-import") (part "rcl_334_R-US_M0805"))
    )
    (comp (ref "R8-5P")
      (value "27K")
      (footprint "eagle-import:M0805")
      (libsource (lib "eagle-import") (part "rcl_334_R-US_M0805"))
    )
    (comp (ref "R8-6P")
      (value "27K")
      (footprint "eagle-import:M0805")
      (libsource (lib "eagle-import") (part "rcl_334_R-US_M0805"))
    )
    (comp (ref "S0-0C")
      (value "DISARM")
      (footprint "eagle-import:B3F-10XX")
      (fields (field (name "MPN") "B3F-1000"))
      (libsource (lib "eagle-import") (part "10-XX"))
    )
    (comp (ref "S1-0C")
      (value "10-XX")
      (footprint "eagle-import:B3F-10XX")
      (fields (field (name "MPN") "B3F-1000"))
      (libsource (lib "eagle-import") (part "10-XX"))
    )
    (comp (ref "S1-P")
      (value "EG1218S")
      (footprint "eagle-import:EG1218")
      (libsource (lib "eagle-import") (part "EG1218S"))
    )
    (comp (ref "U0-C")
      (value "STM32F429ZIT6")
      (footprint "eagle-import:QFP50P2200X2200X160-144N")
      (fields (field (name "MOUSER_PART_NUMBER") "511-STM32F429ZIT6"))
      (libsource (lib "eagle-import") (part "STM32F429ZIT6"))
    )
    (comp (ref "U0-S")
      (value "TPS62202")
      (footprint "eagle-import:SOT95P280X145-5")
      (libsource (lib "eagle-import") (part "TPS62202"))
    )
    (comp (ref "U1-C")
      (value "TC58CVG2S0HRAIJ")
      (footprint "eagle-import:SON127P800X600X80-9N")
      (fields (field (name "MOUSER_PART_NUMBER") "757-TC58CVG2S0HRAIJ"))
      (libsource (lib "eagle-import") (part "TC58CVG2S0HRAIJ"))
    )
    (comp (ref "U1-P")
      (value "MCP73831")
      (footprint "eagle-import:SOT95P270X145-5N")
      (fields
        (field (name "MANUFACTURER_PART_NUMBER") "MCP73831T-2ACI/OT")
        (field (name "MOUSER_PART_NUMBER") "579-MCP73831T-2ACIOT")
      )
      (libsource (lib "eagle-import") (part "MCP73831T-2ACI_OT"))
    )
    (comp (ref "U1-S")
      (value "ICM-20948")
      (footprint "eagle-import:QFN40P300X300X105-25T159X175")
      (libsource (lib "eagle-import") (part "ICM-20948"))
    )
    (comp (ref "U2-C")
      (value "ADS1015BQDGSRQ1")
      (footprint "eagle-import:SOP50P490X110-10N")
      (fields (field (name "MOUSER_PART_NUMBER") "595-ADS1015BQDGSRQ1"))
      (libsource (lib "eagle-import") (part "ADS1015BQDGSRQ1"))
    )
    (comp (ref "U2-P")
      (value "ISL91110IRAZ-T7A")
      (footprint "eagle-import:QFN50P400X400X100-21N")
      (libsource (lib "eagle-import") (part "ISL91110IRAZ-T7A"))
    )
    (comp (ref "U2-S")
      (value "MMA1211KEG")
      (footprint "eagle-import:SOIC127P1041X355-16N")
      (libsource (lib "eagle-import") (part "MMA1211KEG"))
    )
    (comp (ref "U3-S")
      (value "MS5607")
      (footprint "eagle-import:MS5607")
      (libsource (lib "eagle-import") (part "MS5607"))
    )
    (comp (ref "U4-S")
      (value "FGPMMOPA6H")
      (footprint "eagle-import:SOIC127P1800X470-20N")
      (libsource (lib "eagle-import") (part "FGPMMOPA6H"))
    )
    (comp (ref "U7-P")
      (value "LM293DR")
      (footprint "eagle-import:SOIC127P600X175-8N")
      (fields (field (name "MOUSER_PART_NUMBER") "595-LM293DR"))
      (libsource (lib "eagle-import") (part "LM293DR"))
    )
    (comp (ref "U8-P")
      (value "LM293DR")
      (footprint "eagle-import:SOIC127P600X175-8N")
      (fields (field (name "MOUSER_PART_NUMBER") "595-LM293DR"))
      (libsource (lib "eagle-import") (part "LM293DR"))
    )
    (comp (ref "U9-P")
      (value "LM3671-ADJ")
      (footprint "eagle-import:SOT95P280X145-5N")
      (fields
        (field (name "MANUFACTURER_PART_NUMBER") "LM3671MFX-ADJ/NOPB")
        (field (name "MOUSER_PART_NUMBER") "926-LM3671MFXADJNOPB")
      )
      (libsource (lib "eagle-import") (part "LM3671MFX-ADJ_NOPB"))
    )
    (comp (ref "U11-S")
      (value "SN74LV1T34")
      (footprint "eagle-import:SOT65P210X110-5")
      (libsource (lib "eagle-import") (part "SN74LV1T34"))
    )
    (comp (ref "U12-S")
      (value "SN74LV1T34")
      (footprint "eagle-import:SOT65P210X110-5")
      (libsource (lib "eagle-import") (part "SN74LV1T34"))
    )
    (comp (ref "U13-S")
      (value "SN74LV1T34")
      (footprint "eagle-import:SOT65P210X110-5")
      (libsource (lib "eagle-import") (part "SN74LV1T34"))
    )
    (comp (ref "U14-S")
      (value "SN74LV1T34")
      (footprint "eagle-import:SOT65P210X110-5")
      (libsource (lib "eagle-import") (part "SN74LV1T34"))
    )
    (comp (ref "VR1-LS1C")
      (value "TRIM_US-LI10")
      (footprint "eagle-import:LI10")
      (libsource (lib "eagle-import") (part "TRIM_US-LI10"))
    )
    (comp (ref "Y1-C")
      (value "NX3225GD-8MHZ-STD-CRA-3")
      (footprint "eagle-import:3.2X2.5_KX-7")
      (libsource (lib "eagle-import") (part "KX-7"))
    )
  )
  (nets
    (net (code "13") (name "/EX_ANT") (class "Default")
      (node (ref "AT1-S") (pin "1") (pinfunction "SIGNAL_1") (pintype "bidirectional"))
      (node (ref "U4-S") (pin "11") (pinfunction "EX_ANT_11") (pintype "bidirectional"))
    )
    (net (code "20") (name "1V8") (class "Default")
      (node (ref "C2-0S") (pin "1") (pinfunction "1_1") (pintype "passive"))
      (node (ref "C2-1S") (pin "1") (pinfunction "1_1") (pintype "passive"))
      (node (ref "C3-1S") (pin "1") (pinfunction "1_1") (pintype "passive"))
      (node (ref "D1-1S") (pin "A") (pinfunction "A_A") (pintype "passive"))
      (node (ref "L1-0S") (pin "P$2") (pinfunction "2_P$2") (pintype "passive"))
      (node (ref "U0-S") (pin "4") (pinfunction "FB_4") (pintype "bidirectional"))
      (node (ref "U1-S") (pin "13") (pinfunction "VDD_13") (pintype "bidirectional"))
      (node (ref "U1-S") (pin "8") (pinfunction "VDDIO_8") (pintype "bidirectional"))
      (node (ref "U12-S") (pin "5") (pinfunction "VCC_5") (pintype "bidirectional"))
      (node (ref "U13-S") (pin "5") (pinfunction "VCC_5") (pintype "bidirectional"))
      (node (ref "U14-S") (pin "5") (pinfunction "VCC_5") (pintype "bidirectional"))
    )
    (net (code "21") (name "3D-FIX") (class "Default")
      (node (ref "D3-4S") (pin "A") (pinfunction "A_A") (pintype "passive"))
      (node (ref "U4-S") (pin "5") (pinfunction "3D-FIX_5") (pintype "bidirectional"))
    )
    (net (code "22") (name "3V3") (class "Default")
      (node (ref "C1-0C") (pin "1") (pinfunction "1_1") (pintype "passive"))
      (node (ref "C1-0S") (pin "1") (pinfunction "1_1") (pintype "passive"))
      (node (ref "C1-2C") (pin "1") (pinfunction "1_1") (pintype "passive"))
      (node (ref "C1-3S") (pin "1") (pinfunction "1_1") (pintype "passive"))
      (node (ref "C1-9P") (pin "1") (pinfunction "1_1") (pintype "passive"))
      (node (ref "C1-C") (pin "1") (pinfunction "1_1") (pintype "passive"))
      (node (ref "C10-0C") (pin "1") (pinfunction "1_1") (pintype "passive"))
      (node (ref "C11-0C") (pin "1") (pinfunction "1_1") (pintype "passive"))
      (node (ref "C12-0C") (pin "1") (pinfunction "1_1") (pintype "passive"))
      (node (ref "C13-0C") (pin "1") (pinfunction "1_1") (pintype "passive"))
      (node (ref "C14-0C") (pin "1") (pinfunction "1_1") (pintype "passive"))
      (node (ref "C2-0C") (pin "1") (pinfunction "1_1") (pintype "passive"))
      (node (ref "C3-0C") (pin "1") (pinfunction "1_1") (pintype "passive"))
      (node (ref "C4-0C") (pin "1") (pinfunction "1_1") (pintype "passive"))
      (node (ref "C4-9P") (pin "1") (pinfunction "1_1") (pintype "passive"))
      (node (ref "C5-0C") (pin "1") (pinfunction "1_1") (pintype "passive"))
      (node (ref "C6-0C") (pin "1") (pinfunction "1_1") (pintype "passive"))
      (node (ref "C7-0C") (pin "1") (pinfunction "1_1") (pintype "passive"))
      (node (ref "C8-0C") (pin "1") (pinfunction "1_1") (pintype "passive"))
      (node (ref "C9-0C") (pin "1") (pinfunction "1_1") (pintype "passive"))
      (node (ref "D1-2S") (pin "A") (pinfunction "A_A") (pintype "passive"))
      (node (ref "D1-3S") (pin "A") (pinfunction "A_A") (pintype "passive"))
      (node (ref "D1-4S") (pin "A") (pinfunction "A_A") (pintype "passive"))
      (node (ref "FB1-0C") (pin "1") (pinfunction "1_1") (pintype "bidirectional"))
      (node (ref "J1-C") (pin "4") (pinfunction "4_4") (pintype "passive"))
      (node (ref "L1-9P") (pin "2") (pinfunction "2_2") (pintype "bidirectional"))
      (node (ref "R1-2C") (pin "1") (pinfunction "1_1") (pintype "passive"))
      (node (ref "R1-9P") (pin "2") (pinfunction "2_2") (pintype "passive"))
      (node (ref "R2-2C") (pin "1") (pinfunction "1_1") (pintype "passive"))
      (node (ref "R3-9P") (pin "2") (pinfunction "2_2") (pintype "passive"))
      (node (ref "R3-J2C") (pin "2") (pinfunction "2_2") (pintype "passive"))
      (node (ref "R4-2C") (pin "1") (pinfunction "1_1") (pintype "passive"))
      (node (ref "S0-0C") (pin "1") (pinfunction "S_1") (pintype "passive"))
      (node (ref "U0-C") (pin "108") (pinfunction "VDD_9_108") (pintype "power_in"))
      (node (ref "U0-C") (pin "121") (pinfunction "VDD_10_121") (pintype "power_in"))
      (node (ref "U0-C") (pin "131") (pinfunction "VDD_11_131") (pintype "power_in"))
      (node (ref "U0-C") (pin "143") (pinfunction "PDR_ON_143") (pintype "bidirectional"))
      (node (ref "U0-C") (pin "144") (pinfunction "VDD_12_144") (pintype "power_in"))
      (node (ref "U0-C") (pin "17") (pinfunction "VDD_1_17") (pintype "power_in"))
      (node (ref "U0-C") (pin "30") (pinfunction "VDD_2_30") (pintype "power_in"))
      (node (ref "U0-C") (pin "39") (pinfunction "VDD_3_39") (pintype "power_in"))
      (node (ref "U0-C") (pin "52") (pinfunction "VDD_4_52") (pintype "power_in"))
      (node (ref "U0-C") (pin "6") (pinfunction "VBAT_6") (pintype "bidirectional"))
      (node (ref "U0-C") (pin "62") (pinfunction "VDD_5_62") (pintype "power_in"))
      (node (ref "U0-C") (pin "72") (pinfunction "VDD_6_72") (pintype "power_in"))
      (node (ref "U0-C") (pin "84") (pinfunction "VDD_7_84") (pintype "power_in"))
      (node (ref "U0-C") (pin "95") (pinfunction "VDD_8_95") (pintype "power_in"))
      (node (ref "U0-S") (pin "1") (pinfunction "VI_1") (pintype "bidirectional"))
      (node (ref "U0-S") (pin "3") (pinfunction "EN_3") (pintype "bidirectional"))
      (node (ref "U1-C") (pin "7") (pinfunction "VCC_7") (pintype "bidirectional"))
      (node (ref "U11-S") (pin "5") (pinfunction "VCC_5") (pintype "bidirectional"))
      (node (ref "U2-C") (pin "8") (pinfunction "VDD_8") (pintype "bidirectional"))
      (node (ref "U3-S") (pin "P$1") (pinfunction "VDD_P$1") (pintype "bidirectional"))
      (node (ref "U4-S") (pin "1") (pinfunction "VCC_1") (pintype "bidirectional"))
      (node (ref "U7-P") (pin "8") (pinfunction "VCC_8") (pintype "bidirectional"))
      (node (ref "U8-P") (pin "8") (pinfunction "VCC_8") (pintype "bidirectional"))
    )
    (net (code "23") (name "5V") (class "Default")
      (node (ref "C2-2S") (pin "1") (pinfunction "1_1") (pintype "passive"))
      (node (ref "C3-2P") (pin "1") (pinfunction "1_1") (pintype "passive"))
      (node (ref "C3-9P") (pin "1") (pinfunction "1_1") (pintype "passive"))
      (node (ref "C4-2P") (pin "1") (pinfunction "1_1") (pintype "passive"))
      (node (ref "C5-2P") (pin "1") (pinfunction "1_1") (pintype "passive"))
      (node (ref "J1-9P") (pin "14") (pinfunction "14_14") (pintype "passive"))
      (node (ref "R1-2P") (pin "2") (pinfunction "2_2") (pintype "passive"))
      (node (ref "U2-P") (pin "17") (pinfunction "VOUT_1_17") (pintype "bidirectional"))
      (node (ref "U2-P") (pin "18") (pinfunction "VOUT_2_18") (pintype "bidirectional"))
      (node (ref "U2-P") (pin "19") (pinfunction "VOUT_3_19") (pintype "bidirectional"))
      (node (ref "U2-P") (pin "20") (pinfunction "VOUT_4_20") (pintype "bidirectional"))
      (node (ref "U2-S") (pin "8") (pinfunction "VDD_8") (pintype "bidirectional"))
      (node (ref "U9-P") (pin "1") (pinfunction "VIN_1") (pintype "bidirectional"))
      (node (ref "U9-P") (pin "3") (pinfunction "EN_3") (pintype "bidirectional"))
      (node (ref "VR1-LS1C") (pin "A") (pinfunction "A_A") (pintype "passive"))
    )
    (net (code "24") (name "ACCEL_ANALOG") (class "Default")
      (node (ref "C1-2S") (pin "1") (pinfunction "1_1") (pintype "passive"))
      (node (ref "R3-2S") (pin "2") (pinfunction "2_2") (pintype "passive"))
      (node (ref "U0-C") (pin "46") (pinfunction "PB0_46") (pintype "bidirectional"))
    )
    (net (code "25") (name "ADC-ERROR") (class "Default")
      (node (ref "D6-C") (pin "A") (pinfunction "A_A") (pintype "passive"))
      (node (ref "U0-C") (pin "59") (pinfunction "PE8_59") (pintype "bidirectional"))
    )
    (net (code "26") (name "ADC_ALERT") (class "Default")
      (node (ref "R4-2C") (pin "2") (pinfunction "2_2") (pintype "passive"))
      (node (ref "U0-C") (pin "98") (pinfunction "PC8_98") (pintype "bidirectional"))
      (node (ref "U2-C") (pin "2") (pinfunction "ALERT/RDY_2") (pintype "bidirectional"))
    )
    (net (code "27") (name "ARMED-LED") (class "Default")
      (node (ref "D0A-C") (pin "A") (pinfunction "A_A") (pintype "passive"))
      (node (ref "D0B-C") (pin "A") (pinfunction "A_A") (pintype "passive"))
      (node (ref "D0C-C") (pin "A") (pinfunction "A_A") (pintype "passive"))
      (node (ref "U0-C") (pin "53") (pinfunction "PF13_53") (pintype "bidirectional"))
    )
    (net (code "28") (name "BATT_MEAS") (class "Default")
      (node (ref "R3-11P") (pin "1") (pinfunction "1_1") (pintype "passive"))
      (node (ref "R4-11P") (pin "2") (pinfunction "2_2") (pintype "passive"))
      (node (ref "U0-C") (pin "47") (pinfunction "PB1_47") (pintype "bidirectional"))
    )
    (net (code "29") (name "BUZZER_OUT") (class "Default")
      (node (ref "R1-LS1C") (pin "1") (pinfunction "1_1") (pintype "passive"))
      (node (ref "U0-C") (pin "1") (pinfunction "PE2_1") (pintype "bidirectional"))
    )
    (net (code "30") (name "CENTRAL-ERROR") (class "Default")
      (node (ref "D2A-C") (pin "A") (pinfunction "A_A") (pintype "passive"))
      (node (ref "D2B-C") (pin "A") (pinfunction "A_A") (pintype "passive"))
      (node (ref "U0-C") (pin "55") (pinfunction "PF15_55") (pintype "bidirectional"))
    )
    (net (code "31") (name "CENTRAL-NOMINAL") (class "Default")
      (node (ref "D1A-C") (pin "A") (pinfunction "A_A") (pintype "passive"))
      (node (ref "D1B-C") (pin "A") (pinfunction "A_A") (pintype "passive"))
      (node (ref "U0-C") (pin "54") (pinfunction "PF14_54") (pintype "bidirectional"))
    )
    (net (code "32") (name "CLK-1") (class "Default")
      (node (ref "U0-C") (pin "41") (pinfunction "PA5_41") (pintype "bidirectional"))
      (node (ref "U13-S") (pin "2") (pinfunction "A_2") (pintype "bidirectional"))
      (node (ref "U3-S") (pin "P$8") (pinfunction "SCLK_P$8") (pintype "bidirectional"))
    )
    (net (code "33") (name "CLK-1V8") (class "Default")
      (node (ref "U1-S") (pin "23") (pinfunction "SCL/SCLK_23") (pintype "bidirectional"))
      (node (ref "U13-S") (pin "4") (pinfunction "Y_4") (pintype "bidirectional"))
    )
    (net (code "34") (name "CLK-3") (class "Default")
      (node (ref "U0-C") (pin "111") (pinfunction "PC10_111") (pintype "bidirectional"))
      (node (ref "U1-C") (pin "6") (pinfunction "SCK_6") (pintype "bidirectional"))
    )
    (net (code "35") (name "CMP_LDO_IN") (class "Default")
      (node (ref "R1-11P") (pin "1") (pinfunction "1_1") (pintype "passive"))
      (node (ref "R2-11P") (pin "2") (pinfunction "2_2") (pintype "passive"))
      (node (ref "U7-P") (pin "3") (pinfunction "1IN+_3") (pintype "bidirectional"))
      (node (ref "U7-P") (pin "5") (pinfunction "2IN+_5") (pintype "bidirectional"))
      (node (ref "U8-P") (pin "3") (pinfunction "1IN+_3") (pintype "bidirectional"))
      (node (ref "U8-P") (pin "5") (pinfunction "2IN+_5") (pintype "bidirectional"))
    )
    (net (code "36") (name "CMP_LDO_OUT_1") (class "Default")
      (node (ref "Q1-5P") (pin "2") (pinfunction "G1_2") (pintype "bidirectional"))
      (node (ref "R2-5P") (pin "2") (pinfunction "2_2") (pintype "passive"))
      (node (ref "U7-P") (pin "1") (pinfunction "1OUT_1") (pintype "bidirectional"))
    )
    (net (code "37") (name "CMP_LDO_OUT_2") (class "Default")
      (node (ref "Q1-5P") (pin "4") (pinfunction "G2_4") (pintype "bidirectional"))
      (node (ref "R6-5P") (pin "2") (pinfunction "2_2") (pintype "passive"))
      (node (ref "U7-P") (pin "7") (pinfunction "2OUT_7") (pintype "bidirectional"))
    )
    (net (code "38") (name "CMP_LDO_OUT_3") (class "Default")
      (node (ref "Q1-6P") (pin "2") (pinfunction "G1_2") (pintype "bidirectional"))
      (node (ref "R2-6P") (pin "2") (pinfunction "2_2") (pintype "passive"))
      (node (ref "U8-P") (pin "1") (pinfunction "1OUT_1") (pintype "bidirectional"))
    )
    (net (code "39") (name "CMP_LDO_OUT_4") (class "Default")
      (node (ref "Q1-6P") (pin "4") (pinfunction "G2_4") (pintype "bidirectional"))
      (node (ref "R6-6P") (pin "2") (pinfunction "2_2") (pintype "passive"))
      (node (ref "U8-P") (pin "7") (pinfunction "2OUT_7") (pintype "bidirectional"))
    )
    (net (code "40") (name "CMP_RAIL") (class "Default")
      (node (ref "R3-9P") (pin "1") (pinfunction "1_1") (pintype "passive"))
      (node (ref "R4-9P") (pin "2") (pinfunction "2_2") (pintype "passive"))
      (node (ref "U7-P") (pin "2") (pinfunction "1IN-_2") (pintype "bidirectional"))
      (node (ref "U7-P") (pin "6") (pinfunction "2IN-_6") (pintype "bidirectional"))
      (node (ref "U8-P") (pin "2") (pinfunction "1IN-_2") (pintype "bidirectional"))
      (node (ref "U8-P") (pin "6") (pinfunction "2IN-_6") (pintype "bidirectional"))
    )
    (net (code "41") (name "CS-3") (class "Default")
      (node (ref "U0-C") (pin "114") (pinfunction "PD0_114") (pintype "bidirectional"))
      (node (ref "U1-C") (pin "1") (pinfunction "~{CS}_1") (pintype "bidirectional"))
    )
    (net (code "42") (name "CS1") (class "Default")
      (node (ref "U0-C") (pin "44") (pinfunction "PC4_44") (pintype "bidirectional"))
      (node (ref "U14-S") (pin "2") (pinfunction "A_2") (pintype "bidirectional"))
    )
    (net (code "43") (name "CS1-1V8") (class "Default")
      (node (ref "U1-S") (pin "22") (pinfunction "NCS_22") (pintype "bidirectional"))
      (node (ref "U14-S") (pin "4") (pinfunction "Y_4") (pintype "bidirectional"))
    )
    (net (code "44") (name "CS2") (class "Default")
      (node (ref "U0-C") (pin "45") (pinfunction "PC5_45") (pintype "bidirectional"))
      (node (ref "U3-S") (pin "P$4") (pinfunction "CSB_P$4") (pintype "bidirectional"))
      (node (ref "U3-S") (pin "P$5") (pinfunction "CSB_P$5") (pintype "bidirectional"))
    )
    (net (code "46") (name "CTS") (class "Default")
      (node (ref "J1-9P") (pin "13") (pinfunction "13_13") (pintype "passive"))
      (node (ref "U0-C") (pin "34") (pinfunction "PA0_34") (pintype "bidirectional"))
    )
    (net (code "47") (name "D+") (class "Default")
      (node (ref "R2-J2C") (pin "2") (pinfunction "2_2") (pintype "passive"))
      (node (ref "R3-J2C") (pin "1") (pinfunction "1_1") (pintype "passive"))
      (node (ref "U0-C") (pin "104") (pinfunction "PA12_104") (pintype "bidirectional"))
    )
    (net (code "48") (name "D-") (class "Default")
      (node (ref "R1-J2C") (pin "2") (pinfunction "2_2") (pintype "passive"))
      (node (ref "U0-C") (pin "103") (pinfunction "PA11_103") (pintype "bidirectional"))
    )
    (net (code "49") (name "DISARM_INPUT") (class "Default")
      (node (ref "R0-0C") (pin "2") (pinfunction "2_2") (pintype "passive"))
      (node (ref "S0-0C") (pin "3") (pinfunction "P_3") (pintype "passive"))
      (node (ref "U0-C") (pin "89") (pinfunction "PG4_89") (pintype "bidirectional"))
    )
    (net (code "50") (name "DROGUE-LED") (class "Default")
      (node (ref "D3-C") (pin "A") (pinfunction "A_A") (pintype "passive"))
      (node (ref "U0-C") (pin "56") (pinfunction "PG0_56") (pintype "bidirectional"))
    )
    (net (code "51") (name "FET_A") (class "Default")
      (node (ref "J2-P") (pin "2") (pinfunction "2_2") (pintype "bidirectional"))
      (node (ref "Q1-5P") (pin "7") (pinfunction "D1_1_7") (pintype "bidirectional"))
      (node (ref "Q1-5P") (pin "8") (pinfunction "D1_2_8") (pintype "bidirectional"))
      (node (ref "R3-5P") (pin "1") (pinfunction "1_1") (pintype "passive"))
    )
    (net (code "52") (name "FET_B") (class "Default")
      (node (ref "J2-P") (pin "4") (pinfunction "4_4") (pintype "bidirectional"))
      (node (ref "Q1-5P") (pin "5") (pinfunction "D2_1_5") (pintype "bidirectional"))
      (node (ref "Q1-5P") (pin "6") (pinfunction "D2_2_6") (pintype "bidirectional"))
      (node (ref "R7-5P") (pin "1") (pinfunction "1_1") (pintype "passive"))
    )
    (net (code "53") (name "FET_C") (class "Default")
      (node (ref "J2-P") (pin "6") (pinfunction "6_6") (pintype "bidirectional"))
      (node (ref "Q1-6P") (pin "7") (pinfunction "D1_1_7") (pintype "bidirectional"))
      (node (ref "Q1-6P") (pin "8") (pinfunction "D1_2_8") (pintype "bidirectional"))
      (node (ref "R3-6P") (pin "1") (pinfunction "1_1") (pintype "passive"))
    )
    (net (code "54") (name "FET_D") (class "Default")
      (node (ref "J2-P") (pin "8") (pinfunction "8_8") (pintype "bidirectional"))
      (node (ref "Q1-6P") (pin "5") (pinfunction "D2_1_5") (pintype "bidirectional"))
      (node (ref "Q1-6P") (pin "6") (pinfunction "D2_2_6") (pintype "bidirectional"))
      (node (ref "R7-6P") (pin "1") (pinfunction "1_1") (pintype "passive"))
    )
    (net (code "55") (name "FIRE_A") (class "Default")
      (node (ref "R1-5P") (pin "2") (pinfunction "2_2") (pintype "passive"))
      (node (ref "R2-5P") (pin "1") (pinfunction "1_1") (pintype "passive"))
      (node (ref "U0-C") (pin "11") (pinfunction "PF1_11") (pintype "bidirectional"))
    )
    (net (code "56") (name "FIRE_B") (class "Default")
      (node (ref "R5-5P") (pin "2") (pinfunction "2_2") (pintype "passive"))
      (node (ref "R6-5P") (pin "1") (pinfunction "1_1") (pintype "passive"))
      (node (ref "U0-C") (pin "12") (pinfunction "PF2_12") (pintype "bidirectional"))
    )
    (net (code "57") (name "FIRE_C") (class "Default")
      (node (ref "R1-6P") (pin "2") (pinfunction "2_2") (pintype "passive"))
      (node (ref "R2-6P") (pin "1") (pinfunction "1_1") (pintype "passive"))
      (node (ref "U0-C") (pin "13") (pinfunction "PF3_13") (pintype "bidirectional"))
    )
    (net (code "58") (name "FIRE_D") (class "Default")
      (node (ref "R5-6P") (pin "2") (pinfunction "2_2") (pintype "passive"))
      (node (ref "R6-6P") (pin "1") (pinfunction "1_1") (pintype "passive"))
      (node (ref "U0-C") (pin "14") (pinfunction "PF4_14") (pintype "bidirectional"))
    )
    (net (code "59") (name "GND") (class "Default")
      (node (ref "1S_LIPO") (pin "2") (pinfunction "2_2") (pintype "bidirectional"))
      (node (ref "AT1-S") (pin "2") (pinfunction "GND_1_2") (pintype "bidirectional"))
      (node (ref "AT1-S") (pin "3") (pinfunction "GND_2_3") (pintype "bidirectional"))
      (node (ref "AT1-S") (pin "4") (pinfunction "GND_3_4") (pintype "bidirectional"))
      (node (ref "C1") (pin "2") (pinfunction "2_2") (pintype "passive"))
      (node (ref "C1-0C") (pin "2") (pinfunction "2_2") (pintype "passive"))
      (node (ref "C1-0S") (pin "2") (pinfunction "2_2") (pintype "passive"))
      (node (ref "C1-11P") (pin "2") (pinfunction "2_2") (pintype "passive"))
      (node (ref "C1-1P") (pin "2") (pinfunction "2_2") (pintype "passive"))
      (node (ref "C1-1S") (pin "2") (pinfunction "2_2") (pintype "passive"))
      (node (ref "C1-2C") (pin "2") (pinfunction "2_2") (pintype "passive"))
      (node (ref "C1-2P") (pin "2") (pinfunction "2_2") (pintype "passive"))
      (node (ref "C1-2S") (pin "2") (pinfunction "2_2") (pintype "passive"))
      (node (ref "C1-3S") (pin "2") (pinfunction "2_2") (pintype "passive"))
      (node (ref "C1-C") (pin "2") (pinfunction "2_2") (pintype "passive"))
      (node (ref "C10-0C") (pin "2") (pinfunction "2_2") (pintype "passive"))
      (node (ref "C11-0C") (pin "2") (pinfunction "2_2") (pintype "passive"))
      (node (ref "C12-0C") (pin "2") (pinfunction "2_2") (pintype "passive"))
      (node (ref "C13-0C") (pin "2") (pinfunction "2_2") (pintype "passive"))
      (node (ref "C14-0C") (pin "2") (pinfunction "2_2") (pintype "passive"))
      (node (ref "C15-0C") (pin "2") (pinfunction "2_2") (pintype "passive"))
      (node (ref "C16-0C") (pin "2") (pinfunction "2_2") (pintype "passive"))
      (node (ref "C17-0C") (pin "2") (pinfunction "2_2") (pintype "passive"))
      (node (ref "C2") (pin "2") (pinfunction "2_2") (pintype "passive"))
      (node (ref "C2-0C") (pin "2") (pinfunction "2_2") (pintype "passive"))
      (node (ref "C2-0S") (pin "2") (pinfunction "2_2") (pintype "passive"))
      (node (ref "C2-1P") (pin "2") (pinfunction "2_2") (pintype "passive"))
      (node (ref "C2-1S") (pin "2") (pinfunction "2_2") (pintype "passive"))
      (node (ref "C2-2P") (pin "2") (pinfunction "2_2") (pintype "passive"))
      (node (ref "C2-2S") (pin "2") (pinfunction "2_2") (pintype "passive"))
      (node (ref "C2-9P") (pin "2") (pinfunction "2_2") (pintype "passive"))
      (node (ref "C3-0C") (pin "2") (pinfunction "2_2") (pintype "passive"))
      (node (ref "C3-1S") (pin "2") (pinfunction "2_2") (pintype "passive"))
      (node (ref "C3-9P") (pin "2") (pinfunction "2_2") (pintype "passive"))
      (node (ref "C4-0C") (pin "2") (pinfunction "2_2") (pintype "passive"))
      (node (ref "C4-2P") (pin "2") (pinfunction "2_2") (pintype "passive"))
      (node (ref "C4-9P") (pin "2") (pinfunction "2_2") (pintype "passive"))
      (node (ref "C5-0C") (pin "2") (pinfunction "2_2") (pintype "passive"))
      (node (ref "C5-2P") (pin "2") (pinfunction "2_2") (pintype "passive"))
      (node (ref "C6-0C") (pin "2") (pinfunction "2_2") (pintype "passive"))
      (node (ref "C7-0C") (pin "2") (pinfunction "2_2") (pintype "passive"))
      (node (ref "C8-0C") (pin "2") (pinfunction "2_2") (pintype "passive"))
      (node (ref "C9-0C") (pin "2") (pinfunction "2_2") (pintype "passive"))
      (node (ref "J1-9P") (pin "15") (pinfunction "15_15") (pintype "passive"))
      (node (ref "J1-C") (pin "1") (pinfunction "1_1") (pintype "passive"))
      (node (ref "J2-C") (pin "5") (pinfunction "GND_5") (pintype "power_in"))
      (node (ref "J2-C") (pin "S1") (pinfunction "SHIELD_S1") (pintype "power_in"))
      (node (ref "J2-C") (pin "S2") (pinfunction "SHIELD_S2") (pintype "power_in"))
      (node (ref "J2-C") (pin "S3") (pinfunction "SHIELD_S3") (pintype "power_in"))
      (node (ref "J2-C") (pin "S4") (pinfunction "SHIELD_S4") (pintype "power_in"))
      (node (ref "LS1-C") (pin "V-") (pinfunction "V-_V-") (pintype "bidirectional"))
      (node (ref "Q1-5P") (pin "1") (pinfunction "S1_1") (pintype "bidirectional"))
      (node (ref "Q1-5P") (pin "3") (pinfunction "S2_3") (pintype "bidirectional"))
      (node (ref "Q1-6P") (pin "1") (pinfunction "S1_1") (pintype "bidirectional"))
      (node (ref "Q1-6P") (pin "3") (pinfunction "S2_3") (pintype "bidirectional"))
      (node (ref "R0-0C") (pin "1") (pinfunction "1_1") (pintype "passive"))
      (node (ref "R0A-C") (pin "2") (pinfunction "2_2") (pintype "passive"))
      (node (ref "R0B-C") (pin "2") (pinfunction "2_2") (pintype "passive"))
      (node (ref "R0C-C") (pin "2") (pinfunction "2_2") (pintype "passive"))
      (node (ref "R1-0C") (pin "2") (pinfunction "2_2") (pintype "passive"))
      (node (ref "R1-1S") (pin "2") (pinfunction "2_2") (pintype "passive"))
      (node (ref "R1-2S") (pin "2") (pinfunction "2_2") (pintype "passive"))
      (node (ref "R1-3S") (pin "2") (pinfunction "2_2") (pintype "passive"))
      (node (ref "R1-4S") (pin "2") (pinfunction "2_2") (pintype "passive"))
      (node (ref "R1-5P") (pin "1") (pinfunction "1_1") (pintype "passive"))
      (node (ref "R1-6P") (pin "1") (pinfunction "1_1") (pintype "passive"))
      (node (ref "R1A-C") (pin "2") (pinfunction "2_2") (pintype "passive"))
      (node (ref "R1A-S") (pin "2") (pinfunction "2_2") (pintype "passive"))
      (node (ref "R1B-C") (pin "2") (pinfunction "2_2") (pintype "passive"))
      (node (ref "R1B-S") (pin "2") (pinfunction "2_2") (pintype "passive"))
      (node (ref "R2-11P") (pin "1") (pinfunction "1_1") (pintype "passive"))
      (node (ref "R2-1P") (pin "1") (pinfunction "1_1") (pintype "passive"))
      (node (ref "R2-1S") (pin "2") (pinfunction "2_2") (pintype "passive"))
      (node (ref "R2-2P") (pin "1") (pinfunction "1_1") (pintype "passive"))
      (node (ref "R2-2S") (pin "2") (pinfunction "2_2") (pintype "passive"))
      (node (ref "R2-3S") (pin "2") (pinfunction "2_2") (pintype "passive"))
      (node (ref "R2-4S") (pin "2") (pinfunction "2_2") (pintype "passive"))
      (node (ref "R2-9P") (pin "1") (pinfunction "1_1") (pintype "passive"))
      (node (ref "R2A-C") (pin "2") (pinfunction "2_2") (pintype "passive"))
      (node (ref "R2A-S") (pin "2") (pinfunction "2_2") (pintype "passive"))
      (node (ref "R2B-C") (pin "2") (pinfunction "2_2") (pintype "passive"))
      (node (ref "R2B-S") (pin "2") (pinfunction "2_2") (pintype "passive"))
      (node (ref "R3-11P") (pin "2") (pinfunction "2_2") (pintype "passive"))
      (node (ref "R3-2C") (pin "1") (pinfunction "1_1") (pintype "passive"))
      (node (ref "R3-4S") (pin "2") (pinfunction "2_2") (pintype "passive"))
      (node (ref "R3-C") (pin "2") (pinfunction "2_2") (pintype "passive"))
      (node (ref "R3-LS1C") (pin "1") (pinfunction "1_1") (pintype "passive"))
      (node (ref "R4-5P") (pin "1") (pinfunction "1_1") (pintype "passive"))
      (node (ref "R4-6P") (pin "1") (pinfunction "1_1") (pintype "passive"))
      (node (ref "R4-9P") (pin "1") (pinfunction "1_1") (pintype "passive"))
      (node (ref "R4-C") (pin "2") (pinfunction "2_2") (pintype "passive"))
      (node (ref "R5-5P") (pin "1") (pinfunction "1_1") (pintype "passive"))
      (node (ref "R5-6P") (pin "1") (pinfunction "1_1") (pintype "passive"))
      (node (ref "R5-C") (pin "2") (pinfunction "2_2") (pintype "passive"))
      (node (ref "R6-C") (pin "2") (pinfunction "2_2") (pintype "passive"))
      (node (ref "R8-5P") (pin "1") (pinfunction "1_1") (pintype "passive"))
      (node (ref "R8-6P") (pin "1") (pinfunction "1_1") (pintype "passive"))
      (node (ref "S1-0C") (pin "3") (pinfunction "P_3") (pintype "passive"))
      (node (ref "S1-0C") (pin "4") (pinfunction "P1_4") (pintype "passive"))
      (node (ref "U0-C") (pin "107") (pinfunction "VSS_7_107") (pintype "power_in"))
      (node (ref "U0-C") (pin "120") (pinfunction "VSS_8_120") (pintype "power_in"))
      (node (ref "U0-C") (pin "130") (pinfunction "VSS_9_130") (pintype "power_in"))
      (node (ref "U0-C") (pin "16") (pinfunction "VSS_1_16") (pintype "power_in"))
      (node (ref "U0-C") (pin "31") (pinfunction "VSSA_31") (pintype "power_in"))
      (node (ref "U0-C") (pin "38") (pinfunction "VSS_2_38") (pintype "power_in"))
      (node (ref "U0-C") (pin "51") (pinfunction "VSS_3_51") (pintype "power_in"))
      (node (ref "U0-C") (pin "61") (pinfunction "VSS_4_61") (pintype "power_in"))
      (node (ref "U0-C") (pin "83") (pinfunction "VSS_5_83") (pintype "power_in"))
      (node (ref "U0-C") (pin "94") (pinfunction "VSS_6_94") (pintype "power_in"))
      (node (ref "U0-S") (pin "2") (pinfunction "GND_2") (pintype "bidirectional"))
      (node (ref "U1-C") (pin "8") (pinfunction "VSS_8") (pintype "bidirectional"))
      (node (ref "U1-P") (pin "2") (pinfunction "VSS_2") (pintype "power_in"))
      (node (ref "U1-S") (pin "18") (pinfunction "GND_18") (pintype "bidirectional"))
      (node (ref "U1-S") (pin "20") (pinfunction "RESV.GND_20") (pintype "bidirectional"))
      (node (ref "U11-S") (pin "3") (pinfunction "GND_3") (pintype "bidirectional"))
      (node (ref "U12-S") (pin "3") (pinfunction "GND_3") (pintype "bidirectional"))
      (node (ref "U13-S") (pin "3") (pinfunction "GND_3") (pintype "bidirectional"))
      (node (ref "U14-S") (pin "3") (pinfunction "GND_3") (pintype "bidirectional"))
      (node (ref "U2-C") (pin "3") (pinfunction "GND_3") (pintype "bidirectional"))
      (node (ref "U2-P") (pin "12") (pinfunction "MODE_12") (pintype "bidirectional"))
      (node (ref "U2-P") (pin "13") (pinfunction "SGND_1_13") (pintype "bidirectional"))
      (node (ref "U2-P") (pin "3") (pinfunction "PGND_3") (pintype "bidirectional"))
      (node (ref "U2-S") (pin "7") (pinfunction "VSS_7") (pintype "bidirectional"))
      (node (ref "U3-S") (pin "P$2") (pinfunction "PS_P$2") (pintype "bidirectional"))
      (node (ref "U3-S") (pin "P$3") (pinfunction "GND_P$3") (pintype "bidirectional"))
      (node (ref "U4-S") (pin "12") (pinfunction "GND_12") (pintype "bidirectional"))
      (node (ref "U4-S") (pin "19") (pinfunction "GND_19") (pintype "bidirectional"))
      (node (ref "U4-S") (pin "3") (pinfunction "GND_3") (pintype "bidirectional"))
      (node (ref "U4-S") (pin "8") (pinfunction "GND_8") (pintype "bidirectional"))
      (node (ref "U7-P") (pin "4") (pinfunction "GND_4") (pintype "bidirectional"))
      (node (ref "U8-P") (pin "4") (pinfunction "GND_4") (pintype "bidirectional"))
      (node (ref "U9-P") (pin "2") (pinfunction "GND_2") (pintype "bidirectional"))
    )
    (net (code "60") (name "HOLD") (class "Default")
      (node (ref "U0-C") (pin "77") (pinfunction "PD8_77") (pintype "bidirectional"))
      (node (ref "U1-C") (pin "5") (pinfunction "~{HOLD}/IO3_5") (pintype "bidirectional"))
    )
    (net (code "61") (name "ID") (class "Default")
      (node (ref "J2-C") (pin "4") (pinfunction "ID_4") (pintype "bidirectional"))
      (node (ref "U0-C") (pin "102") (pinfunction "PA10_102") (pintype "bidirectional"))
    )
    (net (code "62") (name "MAIN-LED") (class "Default")
      (node (ref "D4-C") (pin "A") (pinfunction "A_A") (pintype "passive"))
      (node (ref "U0-C") (pin "57") (pinfunction "PG1_57") (pintype "bidirectional"))
    )
    (net (code "63") (name "MASTER_RX-1") (class "Default")
      (node (ref "U0-C") (pin "97") (pinfunction "PC7_97") (pintype "bidirectional"))
      (node (ref "U4-S") (pin "9") (pinfunction "TX_9") (pintype "bidirectional"))
    )
    (net (code "64") (name "MASTER_RX-2") (class "Default")
      (node (ref "J1-9P") (pin "7") (pinfunction "7_7") (pintype "passive"))
      (node (ref "U0-C") (pin "37") (pinfunction "PA3_37") (pintype "bidirectional"))
    )
    (net (code "65") (name "MASTER_TX-1") (class "Default")
      (node (ref "U0-C") (pin "96") (pinfunction "PC6_96") (pintype "bidirectional"))
      (node (ref "U4-S") (pin "10") (pinfunction "RX_10") (pintype "bidirectional"))
    )
    (net (code "66") (name "MASTER_TX-2") (class "Default")
      (node (ref "J1-9P") (pin "9") (pinfunction "9_9") (pintype "passive"))
      (node (ref "U0-C") (pin "36") (pinfunction "PA2_36") (pintype "bidirectional"))
    )
    (net (code "67") (name "MISO-1") (class "Default")
      (node (ref "U0-C") (pin "42") (pinfunction "PA6_42") (pintype "bidirectional"))
      (node (ref "U11-S") (pin "4") (pinfunction "Y_4") (pintype "bidirectional"))
    )
    (net (code "68") (name "MISO-1V8") (class "Default")
      (node (ref "U1-S") (pin "9") (pinfunction "SDO/AD0_9") (pintype "bidirectional"))
      (node (ref "U11-S") (pin "2") (pinfunction "A_2") (pintype "bidirectional"))
    )
    (net (code "69") (name "MISO-3") (class "Default")
      (node (ref "U0-C") (pin "112") (pinfunction "PC11_112") (pintype "bidirectional"))
      (node (ref "U1-C") (pin "2") (pinfunction "SO/IO1_2") (pintype "bidirectional"))
    )
    (net (code "70") (name "MOSI-1") (class "Default")
      (node (ref "U0-C") (pin "43") (pinfunction "PA7_43") (pintype "bidirectional"))
      (node (ref "U12-S") (pin "2") (pinfunction "A_2") (pintype "bidirectional"))
      (node (ref "U3-S") (pin "P$6") (pinfunction "SDO_P$6") (pintype "bidirectional"))
      (node (ref "U3-S") (pin "P$7") (pinfunction "SDI_P$7") (pintype "bidirectional"))
    )
    (net (code "71") (name "MOSI-1V8") (class "Default")
      (node (ref "U1-S") (pin "24") (pinfunction "SDA/SDI_24") (pintype "bidirectional"))
      (node (ref "U12-S") (pin "4") (pinfunction "Y_4") (pintype "bidirectional"))
    )
    (net (code "72") (name "MOSI-3") (class "Default")
      (node (ref "U0-C") (pin "113") (pinfunction "PC12_113") (pintype "bidirectional"))
      (node (ref "U1-C") (pin "4") (pinfunction "SI/IO0_4") (pintype "bidirectional"))
    )
    (net (code "74") (name "NRST") (class "Default")
      (node (ref "C15-0C") (pin "1") (pinfunction "1_1") (pintype "passive"))
      (node (ref "R2-J1C") (pin "2") (pinfunction "2_2") (pintype "passive"))
      (node (ref "S1-0C") (pin "1") (pinfunction "S_1") (pintype "passive"))
      (node (ref "S1-0C") (pin "2") (pinfunction "S1_2") (pintype "passive"))
      (node (ref "U0-C") (pin "25") (pinfunction "NRST_25") (pintype "input"))
    )
    (net (code "75") (name "Net-(D0A-C-PadC)") (class "Default")
      (node (ref "D0A-C") (pin "C") (pinfunction "C_C") (pintype "passive"))
      (node (ref "R0A-C") (pin "1") (pinfunction "1_1") (pintype "passive"))
    )
    (net (code "76") (name "Net-(D0B-C-PadC)") (class "Default")
      (node (ref "D0B-C") (pin "C") (pinfunction "C_C") (pintype "passive"))
      (node (ref "R0B-C") (pin "1") (pinfunction "1_1") (pintype "passive"))
    )
    (net (code "77") (name "Net-(D0C-C-PadC)") (class "Default")
      (node (ref "D0C-C") (pin "C") (pinfunction "C_C") (pintype "passive"))
      (node (ref "R0C-C") (pin "1") (pinfunction "1_1") (pintype "passive"))
    )
    (net (code "78") (name "Net-(D1-1P-PadC)") (class "Default")
      (node (ref "D1-1P") (pin "C") (pinfunction "C_C") (pintype "passive"))
      (node (ref "R1-1P") (pin "1") (pinfunction "1_1") (pintype "passive"))
    )
    (net (code "79") (name "Net-(D1-1S-PadC)") (class "Default")
      (node (ref "D1-1S") (pin "C") (pinfunction "C_C") (pintype "passive"))
      (node (ref "R1-1S") (pin "1") (pinfunction "1_1") (pintype "passive"))
    )
    (net (code "80") (name "Net-(D1-2S-PadC)") (class "Default")
      (node (ref "D1-2S") (pin "C") (pinfunction "C_C") (pintype "passive"))
      (node (ref "R1-2S") (pin "1") (pinfunction "1_1") (pintype "passive"))
    )
    (net (code "81") (name "Net-(D1-3S-PadC)") (class "Default")
      (node (ref "D1-3S") (pin "C") (pinfunction "C_C") (pintype "passive"))
      (node (ref "R1-3S") (pin "1") (pinfunction "1_1") (pintype "passive"))
    )
    (net (code "82") (name "Net-(D1-4S-PadC)") (class "Default")
      (node (ref "D1-4S") (pin "C") (pinfunction "C_C") (pintype "passive"))
      (node (ref "R1-4S") (pin "1") (pinfunction "1_1") (pintype "passive"))
    )
    (net (code "83") (name "Net-(D1-11P-A)") (class "Default")
      (node (ref "D1-11P") (pin "2") (pinfunction "A_2") (pintype "bidirectional"))
      (node (ref "R4-11P") (pin "1") (pinfunction "1_1") (pintype "passive"))
      (node (ref "S1-P") (pin "S") (pinfunction "S_S") (pintype "passive"))
    )
    (net (code "84") (name "Net-(D1A-C-PadC)") (class "Default")
      (node (ref "D1A-C") (pin "C") (pinfunction "C_C") (pintype "passive"))
      (node (ref "R1A-C") (pin "1") (pinfunction "1_1") (pintype "passive"))
    )
    (net (code "85") (name "Net-(D1A-S-PadC)") (class "Default")
      (node (ref "D1A-S") (pin "C") (pinfunction "C_C") (pintype "passive"))
      (node (ref "R1A-S") (pin "1") (pinfunction "1_1") (pintype "passive"))
    )
    (net (code "86") (name "Net-(D1B-C-PadC)") (class "Default")
      (node (ref "D1B-C") (pin "C") (pinfunction "C_C") (pintype "passive"))
      (node (ref "R1B-C") (pin "1") (pinfunction "1_1") (pintype "passive"))
    )
    (net (code "87") (name "Net-(D1B-S-PadC)") (class "Default")
      (node (ref "D1B-S") (pin "C") (pinfunction "C_C") (pintype "passive"))
      (node (ref "R1B-S") (pin "1") (pinfunction "1_1") (pintype "passive"))
    )
    (net (code "88") (name "Net-(D2-1S-PadC)") (class "Default")
      (node (ref "D2-1S") (pin "C") (pinfunction "C_C") (pintype "passive"))
      (node (ref "R2-1S") (pin "1") (pinfunction "1_1") (pintype "passive"))
    )
    (net (code "89") (name "Net-(D2-2S-PadC)") (class "Default")
      (node (ref "D2-2S") (pin "C") (pinfunction "C_C") (pintype "passive"))
      (node (ref "R2-2S") (pin "1") (pinfunction "1_1") (pintype "passive"))
    )
    (net (code "90") (name "Net-(D2-3S-PadC)") (class "Default")
      (node (ref "D2-3S") (pin "C") (pinfunction "C_C") (pintype "passive"))
      (node (ref "R2-3S") (pin "1") (pinfunction "1_1") (pintype "passive"))
    )
    (net (code "91") (name "Net-(D2-4S-PadC)") (class "Default")
      (node (ref "D2-4S") (pin "C") (pinfunction "C_C") (pintype "passive"))
      (node (ref "R2-4S") (pin "1") (pinfunction "1_1") (pintype "passive"))
    )
    (net (code "92") (name "Net-(D2A-C-PadC)") (class "Default")
      (node (ref "D2A-C") (pin "C") (pinfunction "C_C") (pintype "passive"))
      (node (ref "R2A-C") (pin "1") (pinfunction "1_1") (pintype "passive"))
    )
    (net (code "93") (name "Net-(D2A-S-PadC)") (class "Default")
      (node (ref "D2A-S") (pin "C") (pinfunction "C_C") (pintype "passive"))
      (node (ref "R2A-S") (pin "1") (pinfunction "1_1") (pintype "passive"))
    )
    (net (code "94") (name "Net-(D2B-C-PadC)") (class "Default")
      (node (ref "D2B-C") (pin "C") (pinfunction "C_C") (pintype "passive"))
      (node (ref "R2B-C") (pin "1") (pinfunction "1_1") (pintype "passive"))
    )
    (net (code "95") (name "Net-(D2B-S-PadC)") (class "Default")
      (node (ref "D2B-S") (pin "C") (pinfunction "C_C") (pintype "passive"))
      (node (ref "R2B-S") (pin "1") (pinfunction "1_1") (pintype "passive"))
    )
    (net (code "96") (name "Net-(D3-4S-PadC)") (class "Default")
      (node (ref "D3-4S") (pin "C") (pinfunction "C_C") (pintype "passive"))
      (node (ref "R3-4S") (pin "1") (pinfunction "1_1") (pintype "passive"))
    )
    (net (code "97") (name "Net-(D3-C-PadC)") (class "Default")
      (node (ref "D3-C") (pin "C") (pinfunction "C_C") (pintype "passive"))
      (node (ref "R3-C") (pin "1") (pinfunction "1_1") (pintype "passive"))
    )
    (net (code "98") (name "Net-(D4-C-PadC)") (class "Default")
      (node (ref "D4-C") (pin "C") (pinfunction "C_C") (pintype "passive"))
      (node (ref "R4-C") (pin "1") (pinfunction "1_1") (pintype "passive"))
    )
    (net (code "99") (name "Net-(D5-C-PadC)") (class "Default")
      (node (ref "D5-C") (pin "C") (pinfunction "C_C") (pintype "passive"))
      (node (ref "R5-C") (pin "1") (pinfunction "1_1") (pintype "passive"))
    )
    (net (code "100") (name "Net-(D6-C-PadC)") (class "Default")
      (node (ref "D6-C") (pin "C") (pinfunction "C_C") (pintype "passive"))
      (node (ref "R6-C") (pin "1") (pinfunction "1_1") (pintype "passive"))
    )
    (net (code "101") (name "Net-(J1-C-Pad5)") (class "Default")
      (node (ref "J1-C") (pin "5") (pinfunction "5_5") (pintype "passive"))
      (node (ref "R1-J1C") (pin "1") (pinfunction "1_1") (pintype "passive"))
    )
    (net (code "102") (name "Net-(J1-C-Pad6)") (class "Default")
      (node (ref "J1-C") (pin "6") (pinfunction "6_6") (pintype "passive"))
      (node (ref "R2-J1C") (pin "1") (pinfunction "1_1") (pintype "passive"))
    )
    (net (code "103") (name "Net-(J2-C-D+)") (class "Default")
      (node (ref "J2-C") (pin "3") (pinfunction "D+_3") (pintype "bidirectional"))
      (node (ref "R2-J2C") (pin "1") (pinfunction "1_1") (pintype "passive"))
    )
    (net (code "104") (name "Net-(J2-C-D-)") (class "Default")
      (node (ref "J2-C") (pin "2") (pinfunction "D-_2") (pintype "bidirectional"))
      (node (ref "R1-J2C") (pin "1") (pinfunction "1_1") (pintype "passive"))
    )
    (net (code "105") (name "Net-(L1-0S-1)") (class "Default")
      (node (ref "L1-0S") (pin "P$1") (pinfunction "1_P$1") (pintype "passive"))
      (node (ref "U0-S") (pin "5") (pinfunction "SW_5") (pintype "bidirectional"))
    )
    (net (code "106") (name "Net-(LS1-C-PadV+)") (class "Default")
      (node (ref "LS1-C") (pin "V+") (pinfunction "V+_V+") (pintype "bidirectional"))
      (node (ref "R2-LS1C") (pin "1") (pinfunction "1_1") (pintype "passive"))
    )
    (net (code "107") (name "Net-(Q1-LS1C-B)") (class "Default")
      (node (ref "Q1-LS1C") (pin "1") (pinfunction "B_1") (pintype "passive"))
      (node (ref "R1-LS1C") (pin "2") (pinfunction "2_2") (pintype "passive"))
    )
    (net (code "108") (name "Net-(Q1-LS1C-C)") (class "Default")
      (node (ref "Q1-LS1C") (pin "2") (pinfunction "C_2") (pintype "passive"))
      (node (ref "VR1-LS1C") (pin "S") (pinfunction "S_S") (pintype "passive"))
    )
    (net (code "109") (name "Net-(Q1-LS1C-E)") (class "Default")
      (node (ref "Q1-LS1C") (pin "3") (pinfunction "E_3") (pintype "passive"))
      (node (ref "R2-LS1C") (pin "2") (pinfunction "2_2") (pintype "passive"))
    )
    (net (code "110") (name "Net-(R3-LS1C-Pad2)") (class "Default")
      (node (ref "R3-LS1C") (pin "2") (pinfunction "2_2") (pintype "passive"))
      (node (ref "VR1-LS1C") (pin "E") (pinfunction "E_E") (pintype "passive"))
    )
    (net (code "111") (name "Net-(U0-C-BOOT0)") (class "Default")
      (node (ref "R1-0C") (pin "1") (pinfunction "1_1") (pintype "passive"))
      (node (ref "U0-C") (pin "138") (pinfunction "BOOT0_138") (pintype "bidirectional"))
    )
    (net (code "112") (name "Net-(U0-C-VCAP_1)") (class "Default")
      (node (ref "C16-0C") (pin "1") (pinfunction "1_1") (pintype "passive"))
      (node (ref "U0-C") (pin "71") (pinfunction "VCAP_1_71") (pintype "bidirectional"))
    )
    (net (code "113") (name "Net-(U0-C-VCAP_2)") (class "Default")
      (node (ref "C17-0C") (pin "1") (pinfunction "1_1") (pintype "passive"))
      (node (ref "U0-C") (pin "106") (pinfunction "VCAP_2_106") (pintype "bidirectional"))
    )
    (net (code "114") (name "Net-(U1-P-PROG)") (class "Default")
      (node (ref "R2-1P") (pin "2") (pinfunction "2_2") (pintype "passive"))
      (node (ref "U1-P") (pin "5") (pinfunction "PROG_5") (pintype "bidirectional"))
    )
    (net (code "115") (name "Net-(U1-P-STAT)") (class "Default")
      (node (ref "R1-1P") (pin "2") (pinfunction "2_2") (pintype "passive"))
      (node (ref "U1-P") (pin "1") (pinfunction "STAT_1") (pintype "bidirectional"))
    )
    (net (code "116") (name "Net-(U1-S-REGOUT)") (class "Default")
      (node (ref "C1-1S") (pin "1") (pinfunction "1_1") (pintype "passive"))
      (node (ref "U1-S") (pin "10") (pinfunction "REGOUT_10") (pintype "bidirectional"))
    )
    (net (code "117") (name "Net-(U2-C-ADDR)") (class "Default")
      (node (ref "R3-2C") (pin "2") (pinfunction "2_2") (pintype "passive"))
      (node (ref "U2-C") (pin "1") (pinfunction "ADDR_1") (pintype "bidirectional"))
    )
    (net (code "118") (name "Net-(U2-P-LX1_1)") (class "Default")
      (node (ref "L1-2P") (pin "2") (pinfunction "2_2") (pintype "bidirectional"))
      (node (ref "U2-P") (pin "4") (pinfunction "LX1_1_4") (pintype "bidirectional"))
    )
    (net (code "119") (name "Net-(U2-P-LX2_1)") (class "Default")
      (node (ref "L1-2P") (pin "1") (pinfunction "1_1") (pintype "bidirectional"))
      (node (ref "U2-P") (pin "1") (pinfunction "LX2_1_1") (pintype "bidirectional"))
    )
    (net (code "120") (name "Net-(U2-S-VOUT)") (class "Default")
      (node (ref "R3-2S") (pin "1") (pinfunction "1_1") (pintype "passive"))
      (node (ref "U2-S") (pin "5") (pinfunction "VOUT_5") (pintype "bidirectional"))
    )
    (net (code "121") (name "OSC_IN") (class "Default")
      (node (ref "C1") (pin "1") (pinfunction "1_1") (pintype "passive"))
      (node (ref "U0-C") (pin "23") (pinfunction "PH0_23") (pintype "bidirectional"))
      (node (ref "Y1-C") (pin "3") (pinfunction "2_3") (pintype "passive"))
    )
    (net (code "122") (name "OSC_OUT") (class "Default")
      (node (ref "C2") (pin "1") (pinfunction "1_1") (pintype "passive"))
      (node (ref "U0-C") (pin "24") (pinfunction "PH1_24") (pintype "bidirectional"))
      (node (ref "Y1-C") (pin "1") (pinfunction "1_1") (pintype "passive"))
    )
    (net (code "123") (name "RTS") (class "Default")
      (node (ref "J1-9P") (pin "5") (pinfunction "5_5") (pintype "passive"))
      (node (ref "U0-C") (pin "35") (pinfunction "PA1_35") (pintype "bidirectional"))
    )
    (net (code "124") (name "SCL-1") (class "Default")
      (node (ref "R2-2C") (pin "2") (pinfunction "2_2") (pintype "passive"))
      (node (ref "U0-C") (pin "100") (pinfunction "PA8_100") (pintype "bidirectional"))
      (node (ref "U2-C") (pin "10") (pinfunction "SCL_10") (pintype "bidirectional"))
    )
    (net (code "125") (name "SDA-1") (class "Default")
      (node (ref "R1-2C") (pin "2") (pinfunction "2_2") (pintype "passive"))
      (node (ref "U0-C") (pin "99") (pinfunction "PC9_99") (pintype "bidirectional"))
      (node (ref "U2-C") (pin "9") (pinfunction "SDA_9") (pintype "bidirectional"))
    )
    (net (code "126") (name "SENSE_A") (class "Default")
      (node (ref "R3-5P") (pin "2") (pinfunction "2_2") (pintype "passive"))
      (node (ref "R4-5P") (pin "2") (pinfunction "2_2") (pintype "passive"))
      (node (ref "U0-C") (pin "18") (pinfunction "PF6_18") (pintype "bidirectional"))
      (node (ref "U2-C") (pin "4") (pinfunction "AIN0_4") (pintype "bidirectional"))
    )
    (net (code "127") (name "SENSE_B") (class "Default")
      (node (ref "R7-5P") (pin "2") (pinfunction "2_2") (pintype "passive"))
      (node (ref "R8-5P") (pin "2") (pinfunction "2_2") (pintype "passive"))
      (node (ref "U0-C") (pin "19") (pinfunction "PF7_19") (pintype "bidirectional"))
      (node (ref "U2-C") (pin "5") (pinfunction "AIN1_5") (pintype "bidirectional"))
    )
    (net (code "128") (name "SENSE_C") (class "Default")
      (node (ref "R3-6P") (pin "2") (pinfunction "2_2") (pintype "passive"))
      (node (ref "R4-6P") (pin "2") (pinfunction "2_2") (pintype "passive"))
      (node (ref "U0-C") (pin "20") (pinfunction "PF8_20") (pintype "bidirectional"))
      (node (ref "U2-C") (pin "6") (pinfunction "AIN2_6") (pintype "bidirectional"))
    )
    (net (code "129") (name "SENSE_D") (class "Default")
      (node (ref "R7-6P") (pin "2") (pinfunction "2_2") (pintype "passive"))
      (node (ref "R8-6P") (pin "2") (pinfunction "2_2") (pintype "passive"))
      (node (ref "U0-C") (pin "21") (pinfunction "PF9_21") (pintype "bidirectional"))
      (node (ref "U2-C") (pin "7") (pinfunction "AIN3_7") (pintype "bidirectional"))
    )
    (net (code "130") (name "SENSOR-ERROR") (class "Default")
      (node (ref "D2A-S") (pin "A") (pinfunction "A_A") (pintype "passive"))
      (node (ref "D2B-S") (pin "A") (pinfunction "A_A") (pintype "passive"))
      (node (ref "U0-C") (pin "64") (pinfunction "PE11_64") (pintype "bidirectional"))
    )
    (net (code "131") (name "SENSOR-NOMINAL") (class "Default")
      (node (ref "D1A-S") (pin "A") (pinfunction "A_A") (pintype "passive"))
      (node (ref "D1B-S") (pin "A") (pinfunction "A_A") (pintype "passive"))
      (node (ref "U0-C") (pin "63") (pinfunction "PE10_63") (pintype "bidirectional"))
    )
    (net (code "132") (name "STORAGE-ERROR") (class "Default")
      (node (ref "D5-C") (pin "A") (pinfunction "A_A") (pintype "passive"))
      (node (ref "U0-C") (pin "58") (pinfunction "PE7_58") (pintype "bidirectional"))
    )
    (net (code "133") (name "SWCLK") (class "Default")
      (node (ref "J1-C") (pin "2") (pinfunction "2_2") (pintype "passive"))
      (node (ref "R4-J1C") (pin "1") (pinfunction "1_1") (pintype "passive"))
      (node (ref "R4-J1C") (pin "2") (pinfunction "2_2") (pintype "passive"))
      (node (ref "U0-C") (pin "109") (pinfunction "PA14_109") (pintype "bidirectional"))
    )
    (net (code "134") (name "SWDIO") (class "Default")
      (node (ref "J1-C") (pin "3") (pinfunction "3_3") (pintype "passive"))
      (node (ref "R3-J1C") (pin "1") (pinfunction "1_1") (pintype "passive"))
      (node (ref "R3-J1C") (pin "2") (pinfunction "2_2") (pintype "passive"))
      (node (ref "U0-C") (pin "105") (pinfunction "PA13_105") (pintype "bidirectional"))
    )
    (net (code "135") (name "SWO") (class "Default")
      (node (ref "R1-J1C") (pin "2") (pinfunction "2_2") (pintype "passive"))
      (node (ref "U0-C") (pin "133") (pinfunction "PB3_133") (pintype "bidirectional"))
    )
    (net (code "136") (name "U1S-CHECK") (class "Default")
      (node (ref "D2-1S") (pin "A") (pinfunction "A_A") (pintype "passive"))
      (node (ref "U0-C") (pin "65") (pinfunction "PE12_65") (pintype "bidirectional"))
    )
    (net (code "137") (name "U2P-FB") (class "Default")
      (node (ref "C3-2P") (pin "2") (pinfunction "2_2") (pintype "passive"))
      (node (ref "R1-2P") (pin "1") (pinfunction "1_1") (pintype "passive"))
      (node (ref "R2-2P") (pin "2") (pinfunction "2_2") (pintype "passive"))
      (node (ref "U2-P") (pin "15") (pinfunction "FB_15") (pintype "bidirectional"))
    )
    (net (code "138") (name "U2S-CHECK") (class "Default")
      (node (ref "D2-2S") (pin "A") (pinfunction "A_A") (pintype "passive"))
      (node (ref "U0-C") (pin "66") (pinfunction "PE13_66") (pintype "bidirectional"))
    )
    (net (code "139") (name "U2S-ST") (class "Default")
      (node (ref "U0-C") (pin "69") (pinfunction "PB10_69") (pintype "bidirectional"))
      (node (ref "U2-S") (pin "4") (pinfunction "ST_4") (pintype "bidirectional"))
    )
    (net (code "141") (name "U3S-CHECK") (class "Default")
      (node (ref "D2-3S") (pin "A") (pinfunction "A_A") (pintype "passive"))
      (node (ref "U0-C") (pin "67") (pinfunction "PE14_67") (pintype "bidirectional"))
    )
    (net (code "143") (name "U4S-CHECK") (class "Default")
      (node (ref "D2-4S") (pin "A") (pinfunction "A_A") (pintype "passive"))
      (node (ref "U0-C") (pin "68") (pinfunction "PE15_68") (pintype "bidirectional"))
    )
    (net (code "144") (name "U9P-FB") (class "Default")
      (node (ref "C1-9P") (pin "2") (pinfunction "2_2") (pintype "passive"))
      (node (ref "C2-9P") (pin "1") (pinfunction "1_1") (pintype "passive"))
      (node (ref "R1-9P") (pin "1") (pinfunction "1_1") (pintype "passive"))
      (node (ref "R2-9P") (pin "2") (pinfunction "2_2") (pintype "passive"))
      (node (ref "U9-P") (pin "4") (pinfunction "FB_4") (pintype "bidirectional"))
    )
    (net (code "145") (name "U9P-SW") (class "Default")
      (node (ref "L1-9P") (pin "1") (pinfunction "1_1") (pintype "bidirectional"))
      (node (ref "U9-P") (pin "5") (pinfunction "SW_5") (pintype "bidirectional"))
    )
    (net (code "146") (name "US2-STATUS") (class "Default")
      (node (ref "U0-C") (pin "70") (pinfunction "PB11_70") (pintype "bidirectional"))
      (node (ref "U2-S") (pin "6") (pinfunction "STATUS_6") (pintype "bidirectional"))
    )
    (net (code "147") (name "VBAT") (class "Default")
      (node (ref "1S_LIPO") (pin "1") (pinfunction "1_1") (pintype "bidirectional"))
      (node (ref "C2-1P") (pin "1") (pinfunction "1_1") (pintype "passive"))
      (node (ref "J2-P") (pin "1") (pinfunction "1_1") (pintype "bidirectional"))
      (node (ref "J2-P") (pin "3") (pinfunction "3_3") (pintype "bidirectional"))
      (node (ref "J2-P") (pin "5") (pinfunction "5_5") (pintype "bidirectional"))
      (node (ref "J2-P") (pin "7") (pinfunction "7_7") (pintype "bidirectional"))
      (node (ref "S1-P") (pin "P") (pinfunction "P_P") (pintype "passive"))
      (node (ref "U1-P") (pin "3") (pinfunction "VBAT_3") (pintype "bidirectional"))
    )
    (net (code "148") (name "VDDA") (class "Default")
      (node (ref "FB1-0C") (pin "2") (pinfunction "2_2") (pintype "bidirectional"))
      (node (ref "U0-C") (pin "32") (pinfunction "VREF+_32") (pintype "input"))
      (node (ref "U0-C") (pin "33") (pinfunction "VDDA_33") (pintype "power_in"))
    )
    (net (code "149") (name "VUSB") (class "Default")
      (node (ref "C1-1P") (pin "1") (pinfunction "1_1") (pintype "passive"))
      (node (ref "D1-1P") (pin "A") (pinfunction "A_A") (pintype "passive"))
      (node (ref "J2-C") (pin "1") (pinfunction "VBUS_1") (pintype "power_in"))
      (node (ref "U1-P") (pin "4") (pinfunction "VDD_4") (pintype "power_in"))
    )
    (net (code "150") (name "V_LDO_IN") (class "Default")
      (node (ref "C1-11P") (pin "1") (pinfunction "1_1") (pintype "passive"))
      (node (ref "C1-2P") (pin "1") (pinfunction "1_1") (pintype "passive"))
      (node (ref "C2-2P") (pin "1") (pinfunction "1_1") (pintype "passive"))
      (node (ref "D1-11P") (pin "1") (pinfunction "K_1") (pintype "bidirectional"))
      (node (ref "R1-11P") (pin "2") (pinfunction "2_2") (pintype "passive"))
      (node (ref "U2-P") (pin "10") (pinfunction "VIN_10") (pintype "bidirectional"))
      (node (ref "U2-P") (pin "11") (pinfunction "EN_11") (pintype "bidirectional"))
      (node (ref "U2-P") (pin "6") (pinfunction "PVIN_1_6") (pintype "bidirectional"))
      (node (ref "U2-P") (pin "7") (pinfunction "PVIN_2_7") (pintype "bidirectional"))
      (node (ref "U2-P") (pin "8") (pinfunction "PVIN_3_8") (pintype "bidirectional"))
      (node (ref "U2-P") (pin "9") (pinfunction "PVIN_4_9") (pintype "bidirectional"))
    )
    (net (code "151") (name "WP") (class "Default")
      (node (ref "U0-C") (pin "78") (pinfunction "PD9_78") (pintype "bidirectional"))
      (node (ref "U1-C") (pin "3") (pinfunction "~{WP}/IO2_3") (pintype "bidirectional"))
    )
    (net (code "152") (name "unconnected-(J1-9P-Pad1)") (class "Default")
      (node (ref "J1-9P") (pin "1") (pinfunction "1_1") (pintype "passive"))
    )
    (net (code "153") (name "unconnected-(J1-9P-Pad2)") (class "Default")
      (node (ref "J1-9P") (pin "2") (pinfunction "2_2") (pintype "passive"))
    )
    (net (code "154") (name "unconnected-(J1-9P-Pad3)") (class "Default")
      (node (ref "J1-9P") (pin "3") (pinfunction "3_3") (pintype "passive"))
    )
    (net (code "155") (name "unconnected-(J1-9P-Pad4)") (class "Default")
      (node (ref "J1-9P") (pin "4") (pinfunction "4_4") (pintype "passive"))
    )
    (net (code "156") (name "unconnected-(J1-9P-Pad6)") (class "Default")
      (node (ref "J1-9P") (pin "6") (pinfunction "6_6") (pintype "passive"))
    )
    (net (code "157") (name "unconnected-(J1-9P-Pad8)") (class "Default")
      (node (ref "J1-9P") (pin "8") (pinfunction "8_8") (pintype "passive"))
    )
    (net (code "158") (name "unconnected-(J1-9P-Pad10)") (class "Default")
      (node (ref "J1-9P") (pin "10") (pinfunction "10_10") (pintype "passive"))
    )
    (net (code "159") (name "unconnected-(J1-9P-Pad11)") (class "Default")
      (node (ref "J1-9P") (pin "11") (pinfunction "11_11") (pintype "passive"))
    )
    (net (code "160") (name "unconnected-(J1-9P-Pad12)") (class "Default")
      (node (ref "J1-9P") (pin "12") (pinfunction "12_12") (pintype "passive"))
    )
    (net (code "161") (name "unconnected-(J1-9P-Pad16)") (class "Default")
      (node (ref "J1-9P") (pin "16") (pinfunction "16_16") (pintype "passive"))
    )
    (net (code "162") (name "unconnected-(S0-0C-P1-Pad4)") (class "Default")
      (node (ref "S0-0C") (pin "4") (pinfunction "P1_4") (pintype "passive"))
    )
    (net (code "163") (name "unconnected-(S0-0C-S1-Pad2)") (class "Default")
      (node (ref "S0-0C") (pin "2") (pinfunction "S1_2") (pintype "passive"))
    )
    (net (code "164") (name "unconnected-(S1-P-PadO)") (class "Default")
      (node (ref "S1-P") (pin "O") (pinfunction "O_O") (pintype "passive"))
    )
    (net (code "165") (name "unconnected-(U0-C-PA4-Pad40)") (class "Default")
      (node (ref "U0-C") (pin "40") (pinfunction "PA4_40") (pintype "bidirectional"))
    )
    (net (code "166") (name "unconnected-(U0-C-PA9-Pad101)") (class "Default")
      (node (ref "U0-C") (pin "101") (pinfunction "PA9_101") (pintype "bidirectional"))
    )
    (net (code "167") (name "unconnected-(U0-C-PA15-Pad110)") (class "Default")
      (node (ref "U0-C") (pin "110") (pinfunction "PA15_110") (pintype "bidirectional"))
    )
    (net (code "168") (name "unconnected-(U0-C-PB2-Pad48)") (class "Default")
      (node (ref "U0-C") (pin "48") (pinfunction "PB2_48") (pintype "bidirectional"))
    )
    (net (code "169") (name "unconnected-(U0-C-PB4-Pad134)") (class "Default")
      (node (ref "U0-C") (pin "134") (pinfunction "PB4_134") (pintype "bidirectional"))
    )
    (net (code "170") (name "unconnected-(U0-C-PB5-Pad135)") (class "Default")
      (node (ref "U0-C") (pin "135") (pinfunction "PB5_135") (pintype "bidirectional"))
    )
    (net (code "171") (name "unconnected-(U0-C-PB6-Pad136)") (class "Default")
      (node (ref "U0-C") (pin "136") (pinfunction "PB6_136") (pintype "bidirectional"))
    )
    (net (code "172") (name "unconnected-(U0-C-PB7-Pad137)") (class "Default")
      (node (ref "U0-C") (pin "137") (pinfunction "PB7_137") (pintype "bidirectional"))
    )
    (net (code "173") (name "unconnected-(U0-C-PB8-Pad139)") (class "Default")
      (node (ref "U0-C") (pin "139") (pinfunction "PB8_139") (pintype "bidirectional"))
    )
    (net (code "174") (name "unconnected-(U0-C-PB9-Pad140)") (class "Default")
      (node (ref "U0-C") (pin "140") (pinfunction "PB9_140") (pintype "bidirectional"))
    )
    (net (code "175") (name "unconnected-(U0-C-PB12-Pad73)") (class "Default")
      (node (ref "U0-C") (pin "73") (pinfunction "PB12_73") (pintype "bidirectional"))
    )
    (net (code "176") (name "unconnected-(U0-C-PB13-Pad74)") (class "Default")
      (node (ref "U0-C") (pin "74") (pinfunction "PB13_74") (pintype "bidirectional"))
    )
    (net (code "177") (name "unconnected-(U0-C-PB14-Pad75)") (class "Default")
      (node (ref "U0-C") (pin "75") (pinfunction "PB14_75") (pintype "bidirectional"))
    )
    (net (code "178") (name "unconnected-(U0-C-PB15-Pad76)") (class "Default")
      (node (ref "U0-C") (pin "76") (pinfunction "PB15_76") (pintype "bidirectional"))
    )
    (net (code "179") (name "unconnected-(U0-C-PC0-Pad26)") (class "Default")
      (node (ref "U0-C") (pin "26") (pinfunction "PC0_26") (pintype "bidirectional"))
    )
    (net (code "180") (name "unconnected-(U0-C-PC1-Pad27)") (class "Default")
      (node (ref "U0-C") (pin "27") (pinfunction "PC1_27") (pintype "bidirectional"))
    )
    (net (code "181") (name "unconnected-(U0-C-PC2-Pad28)") (class "Default")
      (node (ref "U0-C") (pin "28") (pinfunction "PC2_28") (pintype "bidirectional"))
    )
    (net (code "182") (name "unconnected-(U0-C-PC3-Pad29)") (class "Default")
      (node (ref "U0-C") (pin "29") (pinfunction "PC3_29") (pintype "bidirectional"))
    )
    (net (code "183") (name "unconnected-(U0-C-PC13-Pad7)") (class "Default")
      (node (ref "U0-C") (pin "7") (pinfunction "PC13_7") (pintype "bidirectional"))
    )
    (net (code "184") (name "unconnected-(U0-C-PC14-Pad8)") (class "Default")
      (node (ref "U0-C") (pin "8") (pinfunction "PC14_8") (pintype "bidirectional"))
    )
    (net (code "185") (name "unconnected-(U0-C-PC15-Pad9)") (class "Default")
      (node (ref "U0-C") (pin "9") (pinfunction "PC15_9") (pintype "bidirectional"))
    )
    (net (code "186") (name "unconnected-(U0-C-PD1-Pad115)") (class "Default")
      (node (ref "U0-C") (pin "115") (pinfunction "PD1_115") (pintype "bidirectional"))
    )
    (net (code "187") (name "unconnected-(U0-C-PD2-Pad116)") (class "Default")
      (node (ref "U0-C") (pin "116") (pinfunction "PD2_116") (pintype "bidirectional"))
    )
    (net (code "188") (name "unconnected-(U0-C-PD3-Pad117)") (class "Default")
      (node (ref "U0-C") (pin "117") (pinfunction "PD3_117") (pintype "bidirectional"))
    )
    (net (code "189") (name "unconnected-(U0-C-PD4-Pad118)") (class "Default")
      (node (ref "U0-C") (pin "118") (pinfunction "PD4_118") (pintype "bidirectional"))
    )
    (net (code "190") (name "unconnected-(U0-C-PD5-Pad119)") (class "Default")
      (node (ref "U0-C") (pin "119") (pinfunction "PD5_119") (pintype "bidirectional"))
    )
    (net (code "191") (name "unconnected-(U0-C-PD6-Pad122)") (class "Default")
      (node (ref "U0-C") (pin "122") (pinfunction "PD6_122") (pintype "bidirectional"))
    )
    (net (code "192") (name "unconnected-(U0-C-PD7-Pad123)") (class "Default")
      (node (ref "U0-C") (pin "123") (pinfunction "PD7_123") (pintype "bidirectional"))
    )
    (net (code "193") (name "unconnected-(U0-C-PD10-Pad79)") (class "Default")
      (node (ref "U0-C") (pin "79") (pinfunction "PD10_79") (pintype "bidirectional"))
    )
    (net (code "194") (name "unconnected-(U0-C-PD11-Pad80)") (class "Default")
      (node (ref "U0-C") (pin "80") (pinfunction "PD11_80") (pintype "bidirectional"))
    )
    (net (code "195") (name "unconnected-(U0-C-PD12-Pad81)") (class "Default")
      (node (ref "U0-C") (pin "81") (pinfunction "PD12_81") (pintype "bidirectional"))
    )
    (net (code "196") (name "unconnected-(U0-C-PD13-Pad82)") (class "Default")
      (node (ref "U0-C") (pin "82") (pinfunction "PD13_82") (pintype "bidirectional"))
    )
    (net (code "197") (name "unconnected-(U0-C-PD14-Pad85)") (class "Default")
      (node (ref "U0-C") (pin "85") (pinfunction "PD14_85") (pintype "bidirectional"))
    )
    (net (code "198") (name "unconnected-(U0-C-PD15-Pad86)") (class "Default")
      (node (ref "U0-C") (pin "86") (pinfunction "PD15_86") (pintype "bidirectional"))
    )
    (net (code "199") (name "unconnected-(U0-C-PE0-Pad141)") (class "Default")
      (node (ref "U0-C") (pin "141") (pinfunction "PE0_141") (pintype "bidirectional"))
    )
    (net (code "200") (name "unconnected-(U0-C-PE1-Pad142)") (class "Default")
      (node (ref "U0-C") (pin "142") (pinfunction "PE1_142") (pintype "bidirectional"))
    )
    (net (code "201") (name "unconnected-(U0-C-PE3-Pad2)") (class "Default")
      (node (ref "U0-C") (pin "2") (pinfunction "PE3_2") (pintype "bidirectional"))
    )
    (net (code "202") (name "unconnected-(U0-C-PE4-Pad3)") (class "Default")
      (node (ref "U0-C") (pin "3") (pinfunction "PE4_3") (pintype "bidirectional"))
    )
    (net (code "203") (name "unconnected-(U0-C-PE5-Pad4)") (class "Default")
      (node (ref "U0-C") (pin "4") (pinfunction "PE5_4") (pintype "bidirectional"))
    )
    (net (code "204") (name "unconnected-(U0-C-PE6-Pad5)") (class "Default")
      (node (ref "U0-C") (pin "5") (pinfunction "PE6_5") (pintype "bidirectional"))
    )
    (net (code "205") (name "unconnected-(U0-C-PE9-Pad60)") (class "Default")
      (node (ref "U0-C") (pin "60") (pinfunction "PE9_60") (pintype "bidirectional"))
    )
    (net (code "206") (name "unconnected-(U0-C-PF0-Pad10)") (class "Default")
      (node (ref "U0-C") (pin "10") (pinfunction "PF0_10") (pintype "bidirectional"))
    )
    (net (code "207") (name "unconnected-(U0-C-PF5-Pad15)") (class "Default")
      (node (ref "U0-C") (pin "15") (pinfunction "PF5_15") (pintype "bidirectional"))
    )
    (net (code "208") (name "unconnected-(U0-C-PF10-Pad22)") (class "Default")
      (node (ref "U0-C") (pin "22") (pinfunction "PF10_22") (pintype "bidirectional"))
    )
    (net (code "209") (name "unconnected-(U0-C-PF11-Pad49)") (class "Default")
      (node (ref "U0-C") (pin "49") (pinfunction "PF11_49") (pintype "bidirectional"))
    )
    (net (code "210") (name "unconnected-(U0-C-PF12-Pad50)") (class "Default")
      (node (ref "U0-C") (pin "50") (pinfunction "PF12_50") (pintype "bidirectional"))
    )
    (net (code "211") (name "unconnected-(U0-C-PG2-Pad87)") (class "Default")
      (node (ref "U0-C") (pin "87") (pinfunction "PG2_87") (pintype "bidirectional"))
    )
    (net (code "212") (name "unconnected-(U0-C-PG3-Pad88)") (class "Default")
      (node (ref "U0-C") (pin "88") (pinfunction "PG3_88") (pintype "bidirectional"))
    )
    (net (code "213") (name "unconnected-(U0-C-PG5-Pad90)") (class "Default")
      (node (ref "U0-C") (pin "90") (pinfunction "PG5_90") (pintype "bidirectional"))
    )
    (net (code "214") (name "unconnected-(U0-C-PG6-Pad91)") (class "Default")
      (node (ref "U0-C") (pin "91") (pinfunction "PG6_91") (pintype "bidirectional"))
    )
    (net (code "215") (name "unconnected-(U0-C-PG7-Pad92)") (class "Default")
      (node (ref "U0-C") (pin "92") (pinfunction "PG7_92") (pintype "bidirectional"))
    )
    (net (code "216") (name "unconnected-(U0-C-PG8-Pad93)") (class "Default")
      (node (ref "U0-C") (pin "93") (pinfunction "PG8_93") (pintype "bidirectional"))
    )
    (net (code "217") (name "unconnected-(U0-C-PG9-Pad124)") (class "Default")
      (node (ref "U0-C") (pin "124") (pinfunction "PG9_124") (pintype "bidirectional"))
    )
    (net (code "218") (name "unconnected-(U0-C-PG10-Pad125)") (class "Default")
      (node (ref "U0-C") (pin "125") (pinfunction "PG10_125") (pintype "bidirectional"))
    )
    (net (code "219") (name "unconnected-(U0-C-PG11-Pad126)") (class "Default")
      (node (ref "U0-C") (pin "126") (pinfunction "PG11_126") (pintype "bidirectional"))
    )
    (net (code "220") (name "unconnected-(U0-C-PG12-Pad127)") (class "Default")
      (node (ref "U0-C") (pin "127") (pinfunction "PG12_127") (pintype "bidirectional"))
    )
    (net (code "221") (name "unconnected-(U0-C-PG13-Pad128)") (class "Default")
      (node (ref "U0-C") (pin "128") (pinfunction "PG13_128") (pintype "bidirectional"))
    )
    (net (code "222") (name "unconnected-(U0-C-PG14-Pad129)") (class "Default")
      (node (ref "U0-C") (pin "129") (pinfunction "PG14_129") (pintype "bidirectional"))
    )
    (net (code "223") (name "unconnected-(U0-C-PG15-Pad132)") (class "Default")
      (node (ref "U0-C") (pin "132") (pinfunction "PG15_132") (pintype "bidirectional"))
    )
    (net (code "224") (name "unconnected-(U1-C-EP-Pad9)") (class "Default")
      (node (ref "U1-C") (pin "9") (pinfunction "EP_9") (pintype "bidirectional"))
    )
    (net (code "225") (name "unconnected-(U1-S-AUX_CL-Pad7)") (class "Default")
      (node (ref "U1-S") (pin "7") (pinfunction "AUX_CL_7") (pintype "bidirectional"))
    )
    (net (code "226") (name "unconnected-(U1-S-AUX_DA-Pad21)") (class "Default")
      (node (ref "U1-S") (pin "21") (pinfunction "AUX_DA_21") (pintype "bidirectional"))
    )
    (net (code "227") (name "unconnected-(U1-S-FSYNC-Pad11)") (class "Default")
      (node (ref "U1-S") (pin "11") (pinfunction "FSYNC_11") (pintype "bidirectional"))
    )
    (net (code "228") (name "unconnected-(U1-S-INT1-Pad12)") (class "Default")
      (node (ref "U1-S") (pin "12") (pinfunction "INT1_12") (pintype "bidirectional"))
    )
    (net (code "229") (name "unconnected-(U1-S-NC.1-Pad1)") (class "Default")
      (node (ref "U1-S") (pin "1") (pinfunction "NC.1_1") (pintype "bidirectional"))
    )
    (net (code "230") (name "unconnected-(U1-S-NC.2-Pad2)") (class "Default")
      (node (ref "U1-S") (pin "2") (pinfunction "NC.2_2") (pintype "bidirectional"))
    )
    (net (code "231") (name "unconnected-(U1-S-NC.3-Pad3)") (class "Default")
      (node (ref "U1-S") (pin "3") (pinfunction "NC.3_3") (pintype "bidirectional"))
    )
    (net (code "232") (name "unconnected-(U1-S-NC.4-Pad4)") (class "Default")
      (node (ref "U1-S") (pin "4") (pinfunction "NC.4_4") (pintype "bidirectional"))
    )
    (net (code "233") (name "unconnected-(U1-S-NC.5-Pad5)") (class "Default")
      (node (ref "U1-S") (pin "5") (pinfunction "NC.5_5") (pintype "bidirectional"))
    )
    (net (code "234") (name "unconnected-(U1-S-NC.6-Pad6)") (class "Default")
      (node (ref "U1-S") (pin "6") (pinfunction "NC.6_6") (pintype "bidirectional"))
    )
    (net (code "235") (name "unconnected-(U1-S-NC.14-Pad14)") (class "Default")
      (node (ref "U1-S") (pin "14") (pinfunction "NC.14_14") (pintype "bidirectional"))
    )
    (net (code "236") (name "unconnected-(U1-S-NC.15-Pad15)") (class "Default")
      (node (ref "U1-S") (pin "15") (pinfunction "NC.15_15") (pintype "bidirectional"))
    )
    (net (code "237") (name "unconnected-(U1-S-NC.16-Pad16)") (class "Default")
      (node (ref "U1-S") (pin "16") (pinfunction "NC.16_16") (pintype "bidirectional"))
    )
    (net (code "238") (name "unconnected-(U1-S-NC.17-Pad17)") (class "Default")
      (node (ref "U1-S") (pin "17") (pinfunction "NC.17_17") (pintype "bidirectional"))
    )
    (net (code "239") (name "unconnected-(U1-S-RESV.NC-Pad19)") (class "Default")
      (node (ref "U1-S") (pin "19") (pinfunction "RESV.NC_19") (pintype "bidirectional"))
    )
    (net (code "240") (name "unconnected-(U2-P-EP-Pad21)") (class "Default")
      (node (ref "U2-P") (pin "21") (pinfunction "EP_21") (pintype "bidirectional"))
    )
    (net (code "241") (name "unconnected-(U2-P-LX1_2-Pad5)") (class "Default")
      (node (ref "U2-P") (pin "5") (pinfunction "LX1_2_5") (pintype "bidirectional"))
    )
    (net (code "242") (name "unconnected-(U2-P-LX2_2-Pad2)") (class "Default")
      (node (ref "U2-P") (pin "2") (pinfunction "LX2_2_2") (pintype "bidirectional"))
    )
    (net (code "243") (name "unconnected-(U2-P-NC-Pad16)") (class "Default")
      (node (ref "U2-P") (pin "16") (pinfunction "NC_16") (pintype "no_connect"))
    )
    (net (code "244") (name "unconnected-(U2-P-SGND_2-Pad14)") (class "Default")
      (node (ref "U2-P") (pin "14") (pinfunction "SGND_2_14") (pintype "bidirectional"))
    )
    (net (code "245") (name "unconnected-(U4-S-1PPS-Pad13)") (class "Default")
      (node (ref "U4-S") (pin "13") (pinfunction "1PPS_13") (pintype "bidirectional"))
    )
    (net (code "246") (name "unconnected-(U4-S-NREST-Pad2)") (class "Default")
      (node (ref "U4-S") (pin "2") (pinfunction "NREST_2") (pintype "bidirectional"))
    )
    (net (code "247") (name "unconnected-(U4-S-RTCM-Pad14)") (class "Default")
      (node (ref "U4-S") (pin "14") (pinfunction "RTCM_14") (pintype "bidirectional"))
    )
    (net (code "248") (name "unconnected-(U4-S-VBACKUP-Pad4)") (class "Default")
      (node (ref "U4-S") (pin "4") (pinfunction "VBACKUP_4") (pintype "bidirectional"))
    )
  )
)
